# 261503933xxxx_HW-V2.net
KiCad netlist of a schematic drawn in EAGLE
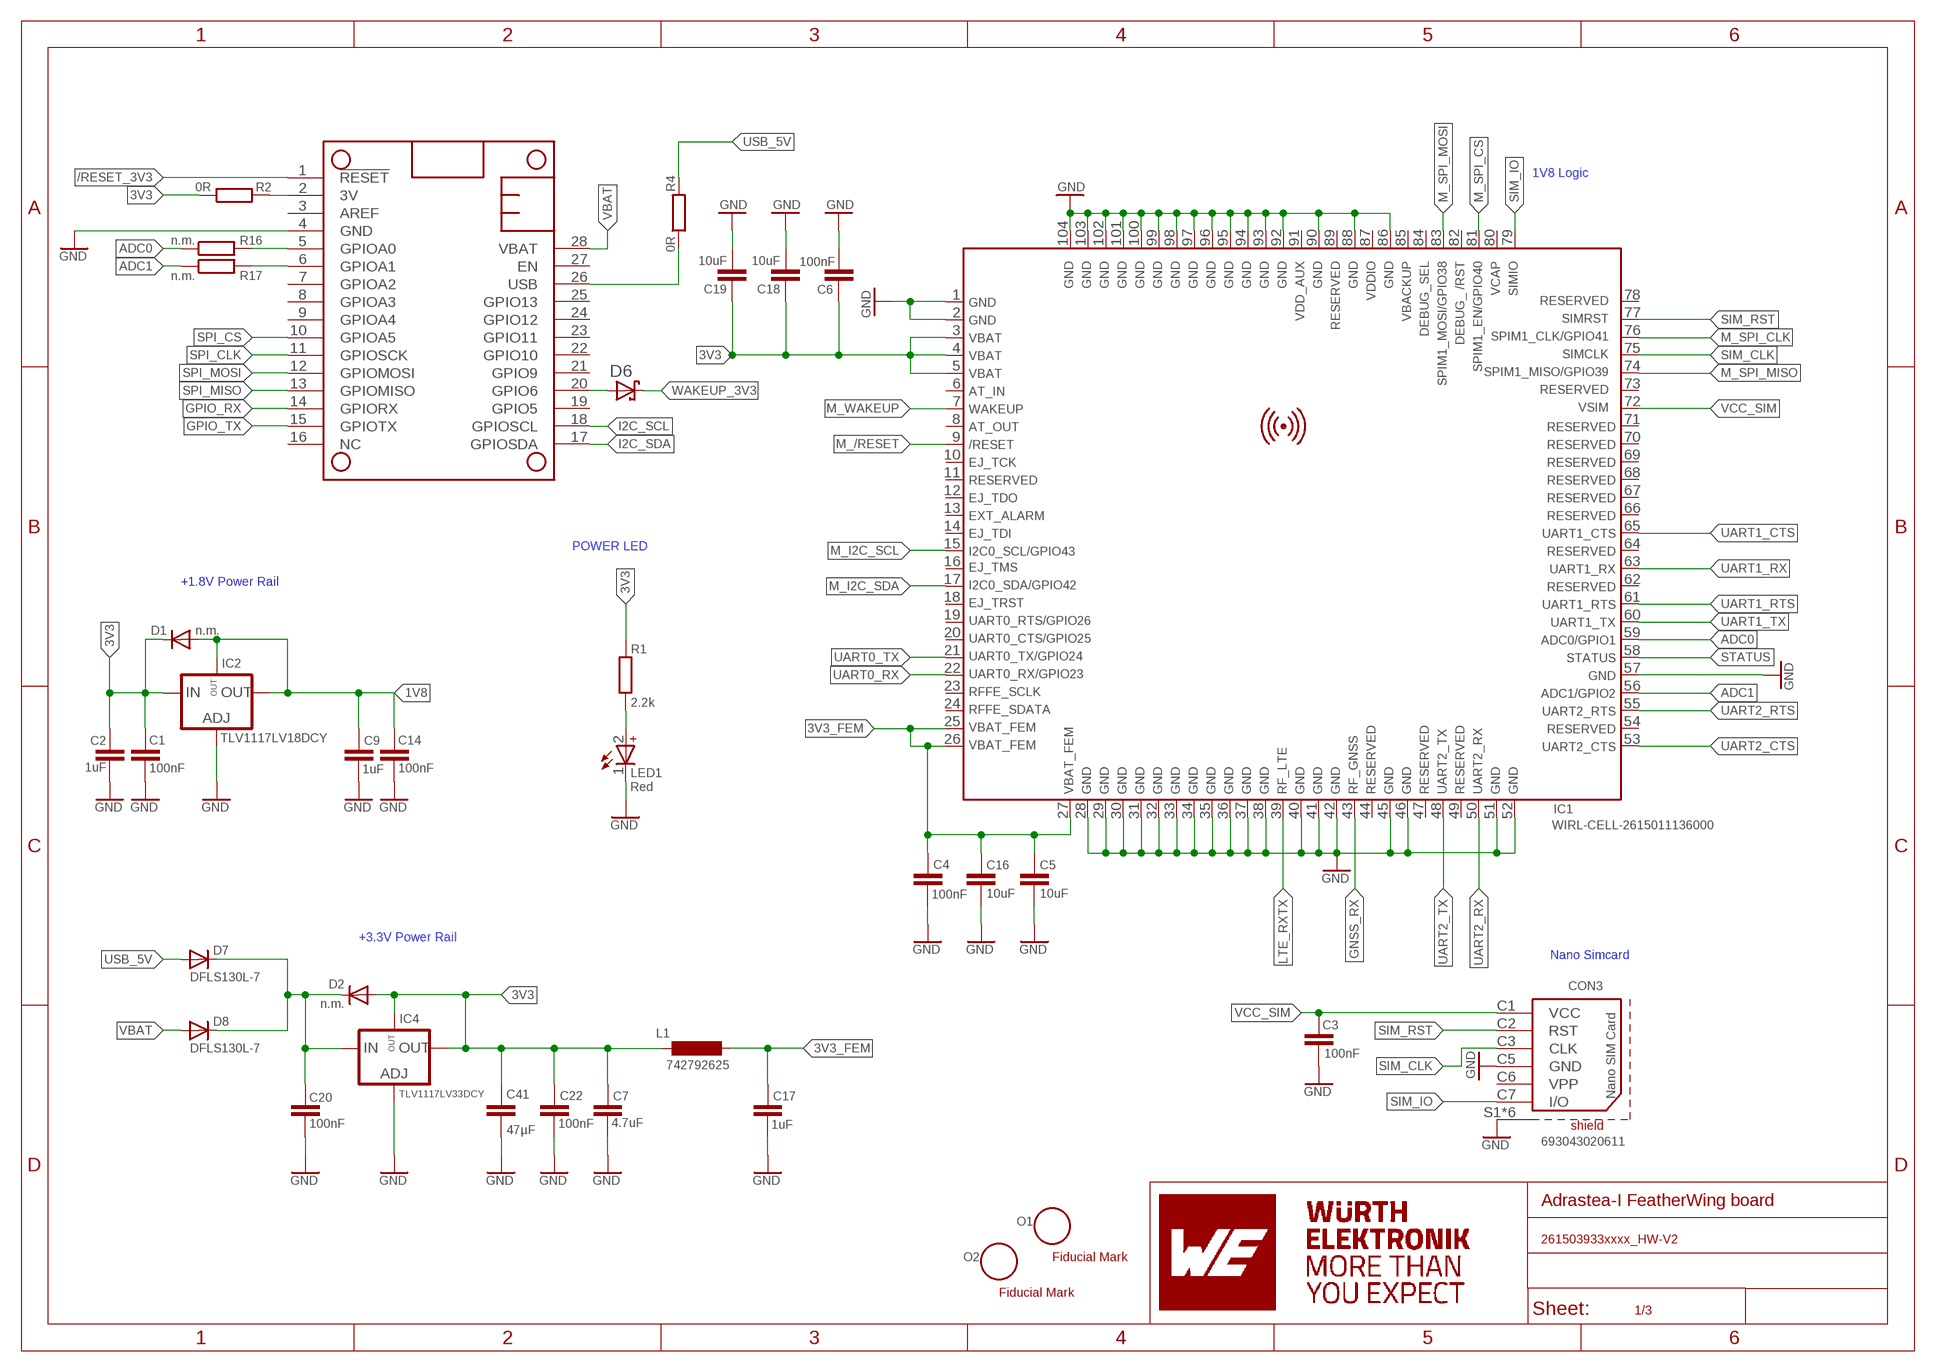
[diagram p0: schematic, sheet 1]
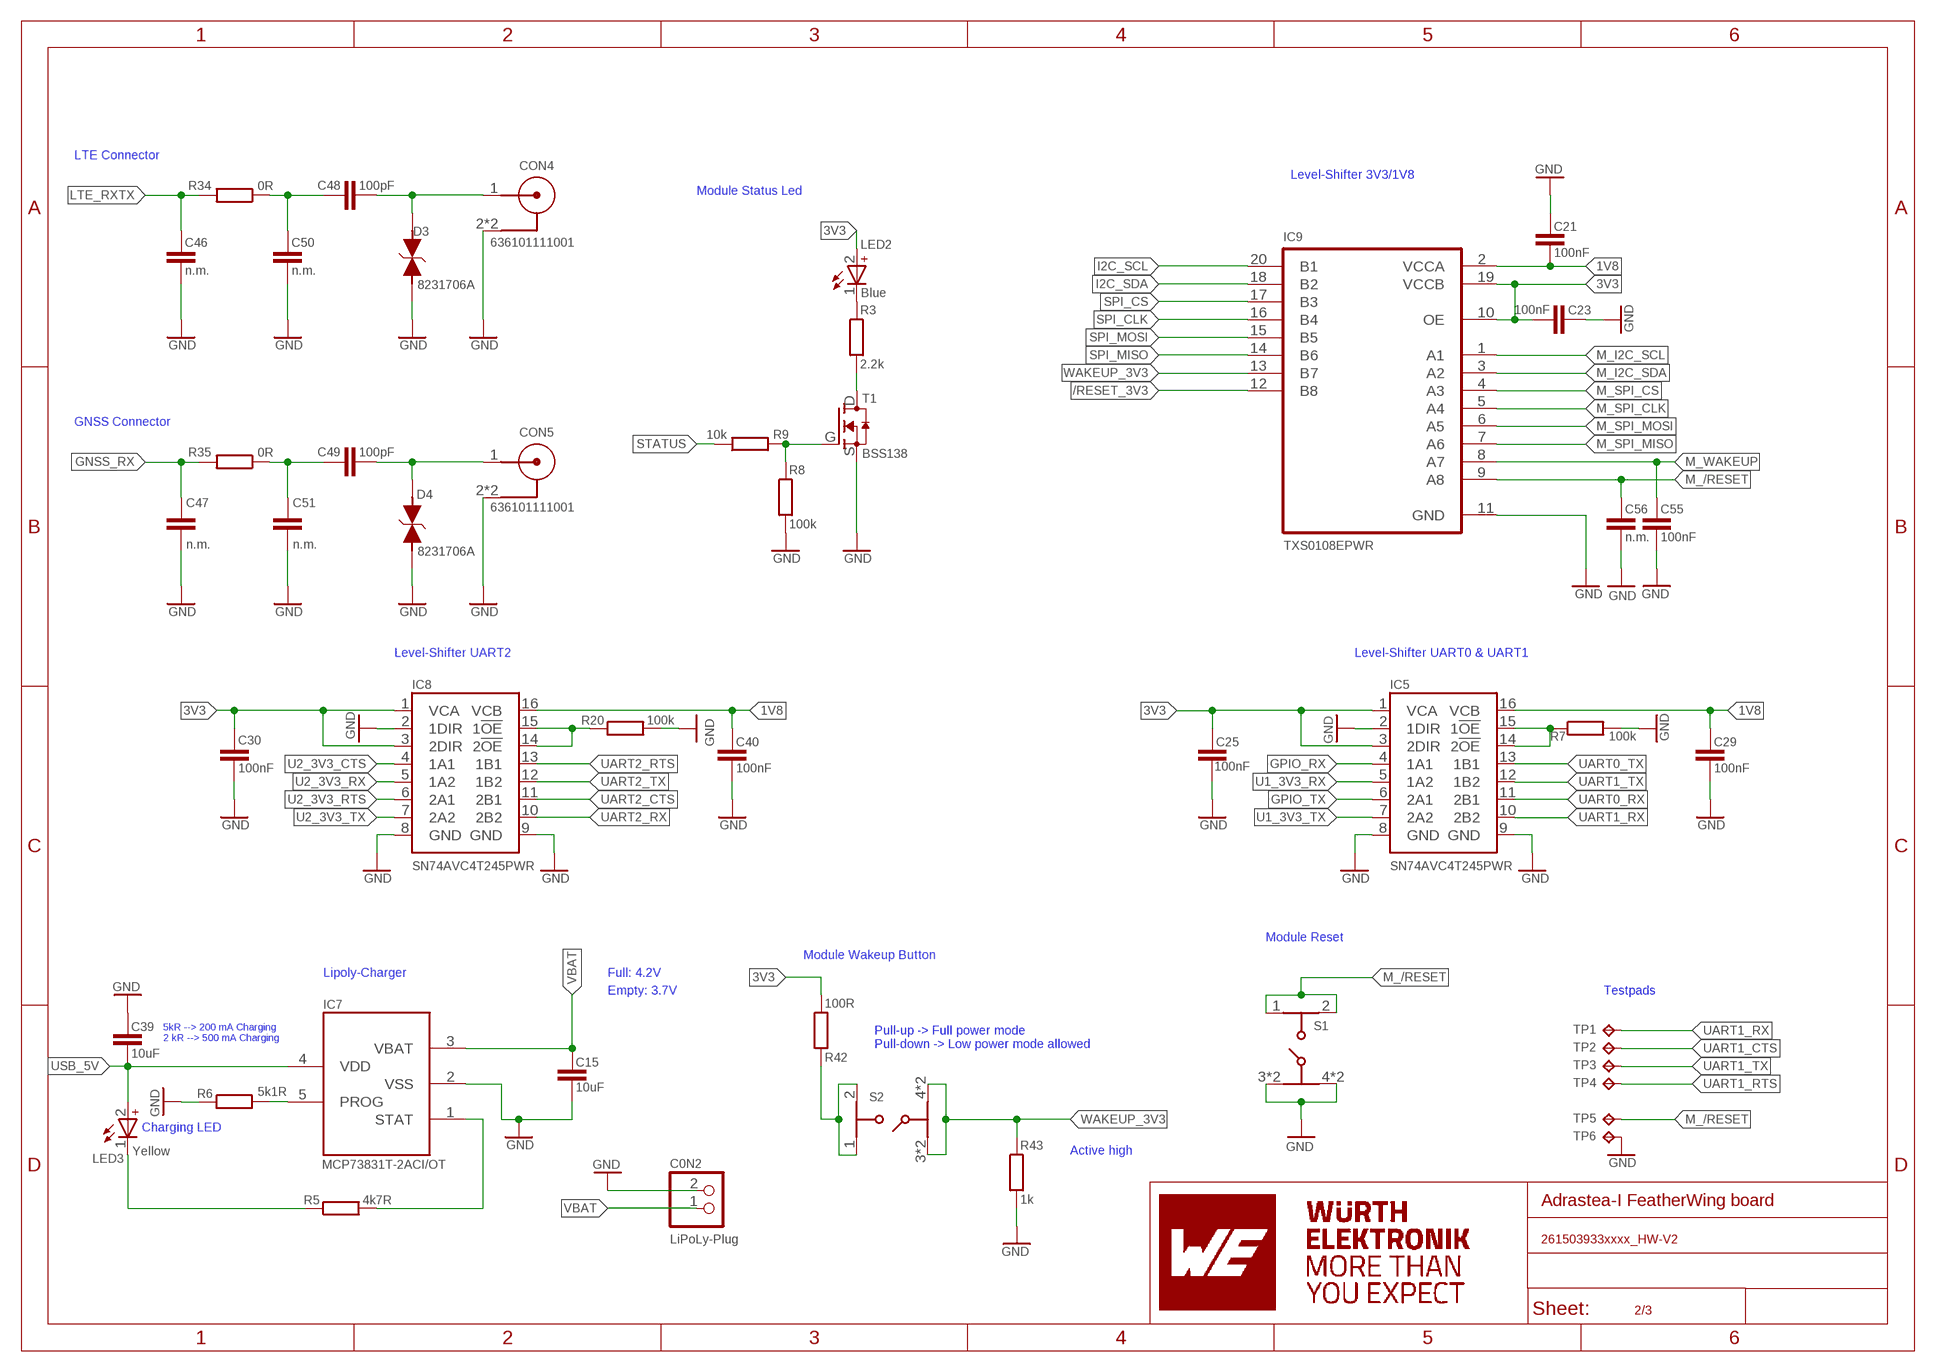
[diagram p1: schematic, sheet 2]
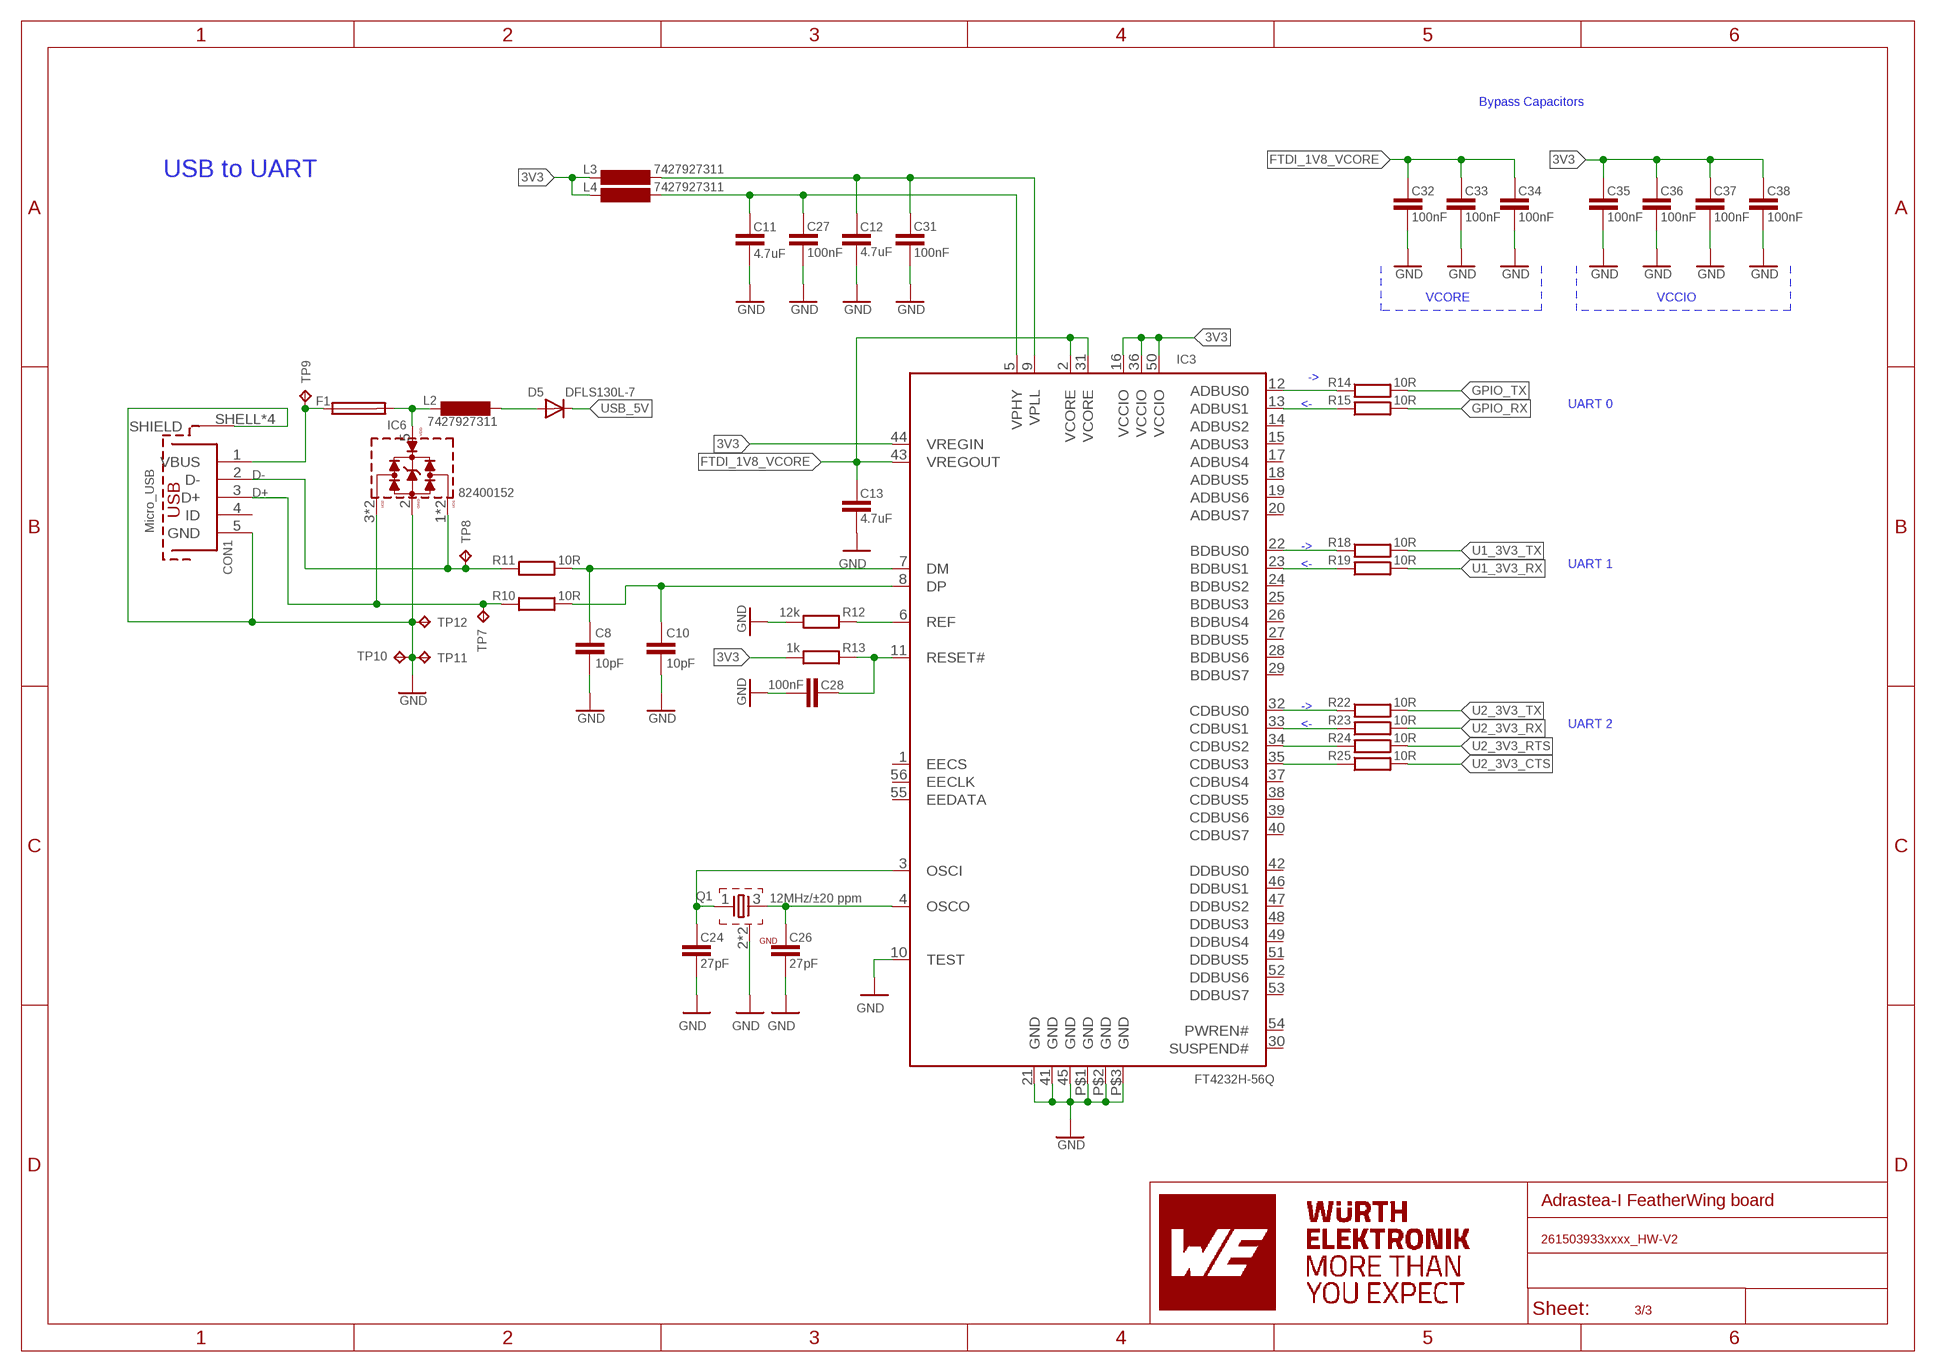
[diagram p2: schematic, sheet 3]

(export (version "E")
  (design (tool "Eeschema 10.0.6"))
  (components
    (comp (ref "C0N2")
      (value "LiPoLy-Plug")
      (footprint "eagle-import:JST-PH-2-SMT-RA-ADRASTEA-ANGEPASST")
      (fields (field (name "MANUFACTURER") "Adafruit"))
      (libsource (lib "eagle-import") (part "JST_2PIN"))
    )
    (comp (ref "C15")
      (value "10uF")
      (footprint "eagle-import:C0402_IPC")
      (fields (field (name "MANUFACTURER") "Würth Elektronik"))
      (libsource (lib "eagle-import") (part "C0402_IPC10UF"))
    )
    (comp (ref "C21")
      (value "100nF")
      (footprint "eagle-import:C0402_IPC")
      (fields
        (field (name "MANUFACTURER") "Würth Elektronik")
        (field (name "MAT") "X7R")
        (field (name "NR") "885012205037")
        (field (name "SPG") "16V")
        (field (name "TOL") "10%")
      )
      (libsource (lib "eagle-import") (part "rcl-amber_C0402_IPC"))
    )
    (comp (ref "C23")
      (value "100nF")
      (footprint "eagle-import:C0402_IPC")
      (fields
        (field (name "MANUFACTURER") "Würth Elektronik")
        (field (name "MAT") "X7R")
        (field (name "NR") "885012205037")
        (field (name "SPG") "16V")
        (field (name "TOL") "10%")
      )
      (libsource (lib "eagle-import") (part "rcl-amber_C0402_IPC"))
    )
    (comp (ref "C25")
      (value "100nF")
      (footprint "eagle-import:C0402_IPC")
      (fields
        (field (name "MANUFACTURER") "Würth Elektronik")
        (field (name "MAT") "X7R")
        (field (name "NR") "885012205037")
        (field (name "SPG") "16V")
        (field (name "TOL") "10%")
      )
      (libsource (lib "eagle-import") (part "rcl-amber_C0402_IPC"))
    )
    (comp (ref "C29")
      (value "100nF")
      (footprint "eagle-import:C0402_IPC")
      (fields
        (field (name "MANUFACTURER") "Würth Elektronik")
        (field (name "MAT") "X7R")
        (field (name "NR") "885012205037")
        (field (name "SPG") "16V")
        (field (name "TOL") "10%")
      )
      (libsource (lib "eagle-import") (part "rcl-amber_C0402_IPC"))
    )
    (comp (ref "C30")
      (value "100nF")
      (footprint "eagle-import:C0402_IPC")
      (fields
        (field (name "MANUFACTURER") "Würth Elektronik")
        (field (name "MAT") "X7R")
        (field (name "NR") "885012205037")
        (field (name "SPG") "16V")
        (field (name "TOL") "10%")
      )
      (libsource (lib "eagle-import") (part "rcl-amber_C0402_IPC"))
    )
    (comp (ref "C39")
      (value "10uF")
      (footprint "eagle-import:C0603_IPC")
      (fields (field (name "MANUFACTURER") "Wurth Elektronik") (field (name "NR") "885012106031"))
      (libsource (lib "eagle-import") (part "C0603_IPC1UF"))
    )
    (comp (ref "C40")
      (value "100nF")
      (footprint "eagle-import:C0402_IPC")
      (fields
        (field (name "MANUFACTURER") "Würth Elektronik")
        (field (name "MAT") "X7R")
        (field (name "NR") "885012205037")
        (field (name "SPG") "16V")
        (field (name "TOL") "10%")
      )
      (libsource (lib "eagle-import") (part "rcl-amber_C0402_IPC"))
    )
    (comp (ref "C46")
      (value "n.m.")
      (footprint "eagle-import:C0402_IPC")
      (fields (field (name "MANUFACTURER") "n.m.") (field (name "NR") "n.m."))
      (libsource (lib "eagle-import") (part "rcl-amber_C0402_IPC"))
    )
    (comp (ref "C47")
      (value "n.m.")
      (footprint "eagle-import:C0402_IPC")
      (fields (field (name "MANUFACTURER") "n.m.") (field (name "NR") "n.m."))
      (libsource (lib "eagle-import") (part "rcl-amber_C0402_IPC"))
    )
    (comp (ref "C48")
      (value "100pF")
      (footprint "eagle-import:C0402_IPC")
      (fields
        (field (name "MANUFACTURER") "Yageo")
        (field (name "MANUFACTURER_1") "Würth Elektronik")
        (field (name "MAT") "NP0")
        (field (name "NR") "885012005061")
      )
      (libsource (lib "eagle-import") (part "rcl-amber_C0402_IPC100PF"))
    )
    (comp (ref "C49")
      (value "100pF")
      (footprint "eagle-import:C0402_IPC")
      (fields
        (field (name "MANUFACTURER") "Würth Elektronik")
        (field (name "MAT") "NP0")
        (field (name "NR") "885012005061")
        (field (name "SPG") "50V")
        (field (name "TOL") "5%")
      )
      (libsource (lib "eagle-import") (part "rcl-amber_C0402_IPC"))
    )
    (comp (ref "C50")
      (value "n.m.")
      (footprint "eagle-import:C0402_IPC")
      (fields (field (name "MANUFACTURER") "n.m.") (field (name "NR") "n.m."))
      (libsource (lib "eagle-import") (part "rcl-amber_C0402_IPC"))
    )
    (comp (ref "C51")
      (value "n.m.")
      (footprint "eagle-import:C0402_IPC")
      (fields (field (name "MANUFACTURER") "n.m.") (field (name "NR") "n.m."))
      (libsource (lib "eagle-import") (part "rcl-amber_C0402_IPC"))
    )
    (comp (ref "C55")
      (value "100nF")
      (footprint "eagle-import:C0402_IPC")
      (fields
        (field (name "MANUFACTURER") "Würth Elektronik")
        (field (name "MAT") "X7R")
        (field (name "NR") "885012205037")
        (field (name "SPG") "16V")
        (field (name "TOL") "10%")
      )
      (libsource (lib "eagle-import") (part "rcl-amber_C0402_IPC"))
    )
    (comp (ref "C56")
      (value "n.m.")
      (footprint "eagle-import:C0402_IPC")
      (fields (field (name "MANUFACTURER") "n.m.") (field (name "NR") "n.m."))
      (libsource (lib "eagle-import") (part "rcl-amber_C0402_IPC"))
    )
    (comp (ref "CON4")
      (value "636101111001")
      (footprint "eagle-import:636101111001")
      (libsource (lib "eagle-import") (part "636101111001"))
    )
    (comp (ref "CON5")
      (value "636101111001")
      (footprint "eagle-import:636101111001")
      (libsource (lib "eagle-import") (part "636101111001"))
    )
    (comp (ref "D3")
      (value "8231706A")
      (footprint "eagle-import:WE-VE_FEMTOF_0402")
      (fields (field (name "MANUFACTURER") "Würth Elektronik"))
      (libsource (lib "eagle-import") (part "WE-VE_FEMTOF_0402_8231714A"))
    )
    (comp (ref "D4")
      (value "8231706A")
      (footprint "eagle-import:WE-VE_FEMTOF_0402")
      (fields (field (name "MANUFACTURER") "Würth Elektronik"))
      (libsource (lib "eagle-import") (part "WE-VE_FEMTOF_0402_8231714A"))
    )
    (comp (ref "IC5")
      (value "SN74AVC4T245PWR")
      (footprint "eagle-import:PW16(TSSOP16)")
      (fields (field (name "MANUFACTURER") "Texas Instruments"))
      (libsource (lib "eagle-import") (part "SN74AVC4T245PWR"))
    )
    (comp (ref "IC7")
      (value "MCP73831T-2ACI/OT")
      (footprint "eagle-import:SOT23-5")
      (fields (field (name "MANUFACTURER") "microchip"))
      (libsource (lib "eagle-import") (part "MCP73831T-2ACI/OT"))
    )
    (comp (ref "IC8")
      (value "SN74AVC4T245PWR")
      (footprint "eagle-import:PW16(TSSOP16)")
      (fields (field (name "MANUFACTURER") "Texas Instruments"))
      (libsource (lib "eagle-import") (part "SN74AVC4T245PWR"))
    )
    (comp (ref "IC9")
      (value "TXS0108EPWR")
      (footprint "eagle-import:SOP65P640X120-20N")
      (fields (field (name "MF") "Texas Instruments"))
      (libsource (lib "eagle-import") (part "TXS0108EPWR"))
    )
    (comp (ref "LED2")
      (value "Blue")
      (footprint "eagle-import:WL-SMSW_1204_A")
      (fields (field (name "MANUFACTURER") "würth elektronik"))
      (libsource (lib "eagle-import") (part "WL-SMSW_1204_155124BS73200"))
    )
    (comp (ref "LED3")
      (value "Yellow")
      (footprint "eagle-import:WL-SMSW_1204_A")
      (fields (field (name "MANUFACTURER") "würth elektronik"))
      (libsource (lib "eagle-import") (part "WL-SMSW_1204_155124RS73200"))
    )
    (comp (ref "R3")
      (value "2.2k")
      (footprint "eagle-import:R0402_IPC")
      (fields (field (name "MANUFACTURER") "Yageo") (field (name "P") "1/16W"))
      (libsource (lib "eagle-import") (part "R0402_IPC2K2"))
    )
    (comp (ref "R5")
      (value "4k7R")
      (footprint "eagle-import:R0402_IPC")
      (fields (field (name "MANUFACTURER") "Yageo"))
      (libsource (lib "eagle-import") (part "R0402_IPC4K7"))
    )
    (comp (ref "R6")
      (value "5k1R")
      (footprint "eagle-import:R0402_IPC")
      (fields (field (name "NR") " RC0402FR-075K1L"))
      (libsource (lib "eagle-import") (part "R0402_IPC56R"))
    )
    (comp (ref "R7")
      (value "100k")
      (footprint "eagle-import:R0402_IPC")
      (libsource (lib "eagle-import") (part "R0402_IPC100KR"))
    )
    (comp (ref "R8")
      (value "100k")
      (footprint "eagle-import:R0402_IPC")
      (fields (field (name "MANUFACTURER") "Yageo") (field (name "P") "1/16W"))
      (libsource (lib "eagle-import") (part "rcl-amber_R0402_IPC100KR"))
    )
    (comp (ref "R9")
      (value "10k")
      (footprint "eagle-import:R0402_IPC")
      (fields (field (name "MANUFACTURER") "Yageo") (field (name "P") "1/16W"))
      (libsource (lib "eagle-import") (part "rcl-amber_R0402_IPC10KR"))
    )
    (comp (ref "R20")
      (value "100k")
      (footprint "eagle-import:R0402_IPC")
      (libsource (lib "eagle-import") (part "R0402_IPC100KR"))
    )
    (comp (ref "R34")
      (value "0R")
      (footprint "eagle-import:R0402_IPC")
      (fields (field (name "MANUFACTURER") "Yageo") (field (name "P") "1/16W"))
      (libsource (lib "eagle-import") (part "rcl-amber_R0402_IPC0R"))
    )
    (comp (ref "R35")
      (value "0R")
      (footprint "eagle-import:R0402_IPC")
      (fields (field (name "MANUFACTURER") "Yageo") (field (name "P") "1/16W"))
      (libsource (lib "eagle-import") (part "rcl-amber_R0402_IPC0R"))
    )
    (comp (ref "R42")
      (value "100R")
      (footprint "eagle-import:R0402_IPC")
      (fields (field (name "MANUFACTURER") "Yageo"))
      (libsource (lib "eagle-import") (part "R0402_IPC100R"))
    )
    (comp (ref "R43")
      (value "1k")
      (footprint "eagle-import:R0402_IPC")
      (fields (field (name "MANUFACTURER") "Yageo") (field (name "P") "1/16W"))
      (libsource (lib "eagle-import") (part "R0402_IPC1K"))
    )
    (comp (ref "S1")
      (value "434331013822")
      (footprint "eagle-import:434331013822")
      (libsource (lib "eagle-import") (part "434331013822"))
    )
    (comp (ref "S2")
      (value "434331013822")
      (footprint "eagle-import:434331013822")
      (libsource (lib "eagle-import") (part "434331013822"))
    )
    (comp (ref "T1")
      (value "BSS138")
      (footprint "eagle-import:BSS138")
      (fields (field (name "MANUFACTURER") "ON seminconductor"))
      (libsource (lib "eagle-import") (part "BSS138"))
    )
    (comp (ref "TP1")
      (value "TP15R")
      (footprint "eagle-import:TP15R")
      (libsource (lib "eagle-import") (part "TP15R"))
    )
    (comp (ref "TP2")
      (value "TP15R")
      (footprint "eagle-import:TP15R")
      (libsource (lib "eagle-import") (part "TP15R"))
    )
    (comp (ref "TP3")
      (value "TP15R")
      (footprint "eagle-import:TP15R")
      (libsource (lib "eagle-import") (part "TP15R"))
    )
    (comp (ref "TP4")
      (value "TP15R")
      (footprint "eagle-import:TP15R")
      (libsource (lib "eagle-import") (part "TP15R"))
    )
    (comp (ref "TP5")
      (value "TP15R")
      (footprint "eagle-import:TP15R")
      (libsource (lib "eagle-import") (part "TP15R"))
    )
    (comp (ref "TP6")
      (value "TP15R")
      (footprint "eagle-import:TP15R")
      (libsource (lib "eagle-import") (part "TP15R"))
    )
    (comp (ref "C8")
      (value "10pF")
      (footprint "eagle-import:C0402_IPC")
      (fields (field (name "MANUFACTURER") "Würth Elektronik") (field (name "MAT") "NP0"))
      (libsource (lib "eagle-import") (part "C0402_IPC10PF"))
    )
    (comp (ref "C10")
      (value "10pF")
      (footprint "eagle-import:C0402_IPC")
      (fields (field (name "MANUFACTURER") "Würth Elektronik") (field (name "MAT") "NP0"))
      (libsource (lib "eagle-import") (part "C0402_IPC10PF"))
    )
    (comp (ref "C11")
      (value "4.7uF")
      (footprint "eagle-import:C0402_IPC")
      (fields (field (name "MANUFACTURER") "Würth Elektronik"))
      (libsource (lib "eagle-import") (part "C0402_IPC4.7UF"))
    )
    (comp (ref "C12")
      (value "4.7uF")
      (footprint "eagle-import:C0402_IPC")
      (fields (field (name "MANUFACTURER") "Würth Elektronik"))
      (libsource (lib "eagle-import") (part "C0402_IPC4.7UF"))
    )
    (comp (ref "C13")
      (value "4.7uF")
      (footprint "eagle-import:C0402_IPC")
      (fields (field (name "MANUFACTURER") "Würth Elektronik"))
      (libsource (lib "eagle-import") (part "C0402_IPC4.7UF"))
    )
    (comp (ref "C24")
      (value "27pF")
      (footprint "eagle-import:C0402_IPC")
      (fields
        (field (name "MANUFACTURER") "Yageo")
        (field (name "MANUFACTURER_1") "Samsung")
        (field (name "NR") "CL05C270JB5NNNC")
      )
      (libsource (lib "eagle-import") (part "C0402_IPC27P"))
    )
    (comp (ref "C26")
      (value "27pF")
      (footprint "eagle-import:C0402_IPC")
      (fields
        (field (name "MANUFACTURER") "Yageo")
        (field (name "MANUFACTURER_1") "Samsung")
        (field (name "NR") "CL05C270JB5NNNC")
      )
      (libsource (lib "eagle-import") (part "C0402_IPC27P"))
    )
    (comp (ref "C27")
      (value "100nF")
      (footprint "eagle-import:C0402_IPC")
      (fields
        (field (name "MANUFACTURER") "Würth Elektronik")
        (field (name "MAT") "X7R")
        (field (name "NR") "885012205037")
        (field (name "SPG") "16V")
        (field (name "TOL") "10%")
      )
      (libsource (lib "eagle-import") (part "rcl-amber_C0402_IPC"))
    )
    (comp (ref "C28")
      (value "100nF")
      (footprint "eagle-import:C0402_IPC")
      (fields
        (field (name "MANUFACTURER") "Würth Elektronik")
        (field (name "MAT") "X7R")
        (field (name "NR") "885012205037")
        (field (name "SPG") "16V")
        (field (name "TOL") "10%")
      )
      (libsource (lib "eagle-import") (part "rcl-amber_C0402_IPC"))
    )
    (comp (ref "C31")
      (value "100nF")
      (footprint "eagle-import:C0402_IPC")
      (fields
        (field (name "MANUFACTURER") "Würth Elektronik")
        (field (name "MAT") "X7R")
        (field (name "NR") "885012205037")
        (field (name "SPG") "16V")
        (field (name "TOL") "10%")
      )
      (libsource (lib "eagle-import") (part "rcl-amber_C0402_IPC"))
    )
    (comp (ref "C32")
      (value "100nF")
      (footprint "eagle-import:C0402_IPC")
      (fields
        (field (name "MANUFACTURER") "Würth Elektronik")
        (field (name "MAT") "X7R")
        (field (name "NR") "885012205037")
        (field (name "SPG") "16V")
        (field (name "TOL") "10%")
      )
      (libsource (lib "eagle-import") (part "rcl-amber_C0402_IPC"))
    )
    (comp (ref "C33")
      (value "100nF")
      (footprint "eagle-import:C0402_IPC")
      (fields
        (field (name "MANUFACTURER") "Würth Elektronik")
        (field (name "MAT") "X7R")
        (field (name "NR") "885012205037")
        (field (name "SPG") "16V")
        (field (name "TOL") "10%")
      )
      (libsource (lib "eagle-import") (part "rcl-amber_C0402_IPC"))
    )
    (comp (ref "C34")
      (value "100nF")
      (footprint "eagle-import:C0402_IPC")
      (fields
        (field (name "MANUFACTURER") "Würth Elektronik")
        (field (name "MAT") "X7R")
        (field (name "NR") "885012205037")
        (field (name "SPG") "16V")
        (field (name "TOL") "10%")
      )
      (libsource (lib "eagle-import") (part "rcl-amber_C0402_IPC"))
    )
    (comp (ref "C35")
      (value "100nF")
      (footprint "eagle-import:C0402_IPC")
      (fields
        (field (name "MANUFACTURER") "Würth Elektronik")
        (field (name "MAT") "X7R")
        (field (name "NR") "885012205037")
        (field (name "SPG") "16V")
        (field (name "TOL") "10%")
      )
      (libsource (lib "eagle-import") (part "rcl-amber_C0402_IPC"))
    )
    (comp (ref "C36")
      (value "100nF")
      (footprint "eagle-import:C0402_IPC")
      (fields
        (field (name "MANUFACTURER") "Würth Elektronik")
        (field (name "MAT") "X7R")
        (field (name "NR") "885012205037")
        (field (name "SPG") "16V")
        (field (name "TOL") "10%")
      )
      (libsource (lib "eagle-import") (part "rcl-amber_C0402_IPC"))
    )
    (comp (ref "C37")
      (value "100nF")
      (footprint "eagle-import:C0402_IPC")
      (fields
        (field (name "MANUFACTURER") "Würth Elektronik")
        (field (name "MAT") "X7R")
        (field (name "NR") "885012205037")
        (field (name "SPG") "16V")
        (field (name "TOL") "10%")
      )
      (libsource (lib "eagle-import") (part "rcl-amber_C0402_IPC"))
    )
    (comp (ref "C38")
      (value "100nF")
      (footprint "eagle-import:C0402_IPC")
      (fields
        (field (name "MANUFACTURER") "Würth Elektronik")
        (field (name "MAT") "X7R")
        (field (name "NR") "885012205037")
        (field (name "SPG") "16V")
        (field (name "TOL") "10%")
      )
      (libsource (lib "eagle-import") (part "rcl-amber_C0402_IPC"))
    )
    (comp (ref "CON1")
      (value "Micro_USB")
      (footprint "eagle-import:629105150521")
      (fields
        (field (name "COMMENT") "Use selective soldering")
        (field (name "MANUFACTURER") "Würth Elektronik")
      )
      (libsource (lib "eagle-import") (part "629105150521"))
    )
    (comp (ref "D5")
      (value "DFLS130L-7")
      (footprint "eagle-import:SOD123_POWERDI")
      (fields (field (name "MANUFACTURER") "diodes inc"))
      (libsource (lib "eagle-import") (part "DFLS130L-7"))
    )
    (comp (ref "F1")
      (value "ERB-RD1R50X")
      (footprint "eagle-import:0402")
      (fields (field (name "MANUFACTURER") "Panasonic"))
      (libsource (lib "eagle-import") (part "ERB-RD1R50X"))
    )
    (comp (ref "IC3")
      (value "FT4232H-56Q")
      (footprint "eagle-import:VQFN-56")
      (fields (field (name "MANUFACTURER") "FTDI"))
      (libsource (lib "eagle-import") (part "FT4232H-56Q"))
    )
    (comp (ref "IC6")
      (value "82400152")
      (footprint "eagle-import:WE-TVS_SOT563")
      (fields (field (name "MANUFACTURER") "Würth Elektronik"))
      (libsource (lib "eagle-import") (part "WE-TVS_82400152"))
    )
    (comp (ref "L2")
      (value "7427927311")
      (footprint "eagle-import:L0402_WE-MK")
      (fields
        (field (name "MANUFACTURER") "Tayo Yuden")
        (field (name "MANUFACTURER_1") "Würth Elektronik")
        (field (name "NR") "7427927311")
      )
      (libsource (lib "eagle-import") (part "LL0402_WE-MK"))
    )
    (comp (ref "L3")
      (value "7427927311")
      (footprint "eagle-import:L0402_WE-MK")
      (fields
        (field (name "MANUFACTURER") "Tayo Yuden")
        (field (name "MANUFACTURER_1") "Würth Elektronik")
        (field (name "NR") "7427927311")
      )
      (libsource (lib "eagle-import") (part "LL0402_WE-MK"))
    )
    (comp (ref "L4")
      (value "7427927311")
      (footprint "eagle-import:L0402_WE-MK")
      (fields
        (field (name "MANUFACTURER") "Tayo Yuden")
        (field (name "MANUFACTURER_1") "Würth Elektronik")
        (field (name "NR") "7427927311")
      )
      (libsource (lib "eagle-import") (part "LL0402_WE-MK"))
    )
    (comp (ref "Q1")
      (value "12MHz/±20 ppm")
      (footprint "eagle-import:WE-XTAL_CFPX-180")
      (fields (field (name "MANUFACTURER") "Würth Elektronik"))
      (libsource (lib "eagle-import") (part "WE-XTAL_CFPX-180_830070868"))
    )
    (comp (ref "R10")
      (value "10R")
      (footprint "eagle-import:R0402_IPC")
      (fields (field (name "MANUFACTURER") "Yageo"))
      (libsource (lib "eagle-import") (part "rcl-amber_R0402_IPC10R"))
    )
    (comp (ref "R11")
      (value "10R")
      (footprint "eagle-import:R0402_IPC")
      (fields (field (name "MANUFACTURER") "Yageo"))
      (libsource (lib "eagle-import") (part "rcl-amber_R0402_IPC10R"))
    )
    (comp (ref "R12")
      (value "12k")
      (footprint "eagle-import:R0402_IPC")
      (fields (field (name "MANUFACTURER") "Yageo") (field (name "P") "1/16W"))
      (libsource (lib "eagle-import") (part "R0402_IPC12K"))
    )
    (comp (ref "R13")
      (value "1k")
      (footprint "eagle-import:R0402_IPC")
      (fields (field (name "MANUFACTURER") "Yageo"))
      (libsource (lib "eagle-import") (part "R0402_IPC1K"))
    )
    (comp (ref "R14")
      (value "10R")
      (footprint "eagle-import:R0402_IPC")
      (fields (field (name "MANUFACTURER") "Yageo"))
      (libsource (lib "eagle-import") (part "rcl-amber_R0402_IPC10R"))
    )
    (comp (ref "R15")
      (value "10R")
      (footprint "eagle-import:R0402_IPC")
      (fields (field (name "MANUFACTURER") "Yageo"))
      (libsource (lib "eagle-import") (part "rcl-amber_R0402_IPC10R"))
    )
    (comp (ref "R18")
      (value "10R")
      (footprint "eagle-import:R0402_IPC")
      (fields (field (name "MANUFACTURER") "Yageo"))
      (libsource (lib "eagle-import") (part "rcl-amber_R0402_IPC10R"))
    )
    (comp (ref "R19")
      (value "10R")
      (footprint "eagle-import:R0402_IPC")
      (fields (field (name "MANUFACTURER") "Yageo"))
      (libsource (lib "eagle-import") (part "rcl-amber_R0402_IPC10R"))
    )
    (comp (ref "R22")
      (value "10R")
      (footprint "eagle-import:R0402_IPC")
      (fields (field (name "MANUFACTURER") "Yageo"))
      (libsource (lib "eagle-import") (part "rcl-amber_R0402_IPC10R"))
    )
    (comp (ref "R23")
      (value "10R")
      (footprint "eagle-import:R0402_IPC")
      (fields (field (name "MANUFACTURER") "Yageo"))
      (libsource (lib "eagle-import") (part "rcl-amber_R0402_IPC10R"))
    )
    (comp (ref "R24")
      (value "10R")
      (footprint "eagle-import:R0402_IPC")
      (fields (field (name "MANUFACTURER") "Yageo"))
      (libsource (lib "eagle-import") (part "rcl-amber_R0402_IPC10R"))
    )
    (comp (ref "R25")
      (value "10R")
      (footprint "eagle-import:R0402_IPC")
      (fields (field (name "MANUFACTURER") "Yageo"))
      (libsource (lib "eagle-import") (part "rcl-amber_R0402_IPC10R"))
    )
    (comp (ref "TP7")
      (value "TP15R")
      (footprint "eagle-import:TP15R")
      (libsource (lib "eagle-import") (part "TP15R"))
    )
    (comp (ref "TP8")
      (value "TP15R")
      (footprint "eagle-import:TP15R")
      (libsource (lib "eagle-import") (part "TP15R"))
    )
    (comp (ref "TP9")
      (value "TP15R")
      (footprint "eagle-import:TP15R")
      (libsource (lib "eagle-import") (part "TP15R"))
    )
    (comp (ref "TP10")
      (value "TP15R")
      (footprint "eagle-import:TP15R")
      (libsource (lib "eagle-import") (part "TP15R"))
    )
    (comp (ref "TP11")
      (value "TP15R")
      (footprint "eagle-import:TP15R")
      (libsource (lib "eagle-import") (part "TP15R"))
    )
    (comp (ref "TP12")
      (value "TP15R")
      (footprint "eagle-import:TP15R")
      (libsource (lib "eagle-import") (part "TP15R"))
    )
    (comp (ref "C1")
      (value "100nF")
      (footprint "eagle-import:C0402_IPC")
      (fields
        (field (name "MANUFACTURER") "Würth Elektronik")
        (field (name "MAT") "X7R")
        (field (name "NR") "885012205037")
        (field (name "SPG") "16V")
        (field (name "TOL") "10%")
      )
      (libsource (lib "eagle-import") (part "rcl-amber_C0402_IPC"))
    )
    (comp (ref "C2")
      (value "1uF")
      (footprint "eagle-import:C0402_IPC")
      (fields (field (name "MANUFACTURER") "Würth Elektronik"))
      (libsource (lib "eagle-import") (part "C0402_IPC1UF"))
    )
    (comp (ref "C3")
      (value "100nF")
      (footprint "eagle-import:C0402_IPC")
      (fields (field (name "MANUFACTURER") "Würth Elektronik"))
      (libsource (lib "eagle-import") (part "C0402_IPC100NF"))
    )
    (comp (ref "C4")
      (value "100nF")
      (footprint "eagle-import:C0402_IPC")
      (fields
        (field (name "MANUFACTURER") "Würth Elektronik")
        (field (name "MAT") "X7R")
        (field (name "NR") "885012205037")
        (field (name "SPG") "16V")
        (field (name "TOL") "10%")
      )
      (libsource (lib "eagle-import") (part "rcl-amber_C0402_IPC"))
    )
    (comp (ref "C5")
      (value "10uF")
      (footprint "eagle-import:C0402_IPC")
      (fields
        (field (name "MANUFACTURER") "Würth Elektronik")
        (field (name "NR") "885012105020")
        (field (name "SPG") "6,3V")
      )
      (libsource (lib "eagle-import") (part "C0402_IPC"))
    )
    (comp (ref "C6")
      (value "100nF")
      (footprint "eagle-import:C0402_IPC")
      (fields
        (field (name "MANUFACTURER") "Würth Elektronik")
        (field (name "MAT") "X7R")
        (field (name "NR") "885012205037")
        (field (name "SPG") "16V")
        (field (name "TOL") "10%")
      )
      (libsource (lib "eagle-import") (part "rcl-amber_C0402_IPC"))
    )
    (comp (ref "C7")
      (value "4.7uF")
      (footprint "eagle-import:C0402_IPC")
      (fields (field (name "MANUFACTURER") "Würth Elektronik"))
      (libsource (lib "eagle-import") (part "C0402_IPC4.7UF"))
    )
    (comp (ref "C9")
      (value "1uF")
      (footprint "eagle-import:C0402_IPC")
      (fields (field (name "MANUFACTURER") "Würth Elektronik"))
      (libsource (lib "eagle-import") (part "C0402_IPC1UF"))
    )
    (comp (ref "C14")
      (value "100nF")
      (footprint "eagle-import:C0402_IPC")
      (fields
        (field (name "MANUFACTURER") "Würth Elektronik")
        (field (name "MAT") "X7R")
        (field (name "NR") "885012205037")
        (field (name "SPG") "16V")
        (field (name "TOL") "10%")
      )
      (libsource (lib "eagle-import") (part "rcl-amber_C0402_IPC"))
    )
    (comp (ref "C16")
      (value "10uF")
      (footprint "eagle-import:C0402_IPC")
      (fields
        (field (name "MANUFACTURER") "Würth Elektronik")
        (field (name "MAT") "X5R")
        (field (name "NR") "885012105020")
        (field (name "SPG") "6,3V")
        (field (name "TOL") "20%")
      )
      (libsource (lib "eagle-import") (part "C0402_IPC"))
    )
    (comp (ref "C17")
      (value "1uF")
      (footprint "eagle-import:C0402_IPC")
      (fields (field (name "MANUFACTURER") "Würth Elektronik"))
      (libsource (lib "eagle-import") (part "C0402_IPC1UF"))
    )
    (comp (ref "C18")
      (value "10uF")
      (footprint "eagle-import:C0402_IPC")
      (fields
        (field (name "MANUFACTURER") "Würth Elektronik")
        (field (name "NR") "885012105020")
        (field (name "SPG") "6,3V")
      )
      (libsource (lib "eagle-import") (part "C0402_IPC"))
    )
    (comp (ref "C19")
      (value "10uF")
      (footprint "eagle-import:C0402_IPC")
      (fields
        (field (name "MANUFACTURER") "Würth Elektronik")
        (field (name "NR") "885012105020")
        (field (name "SPG") "6,3V")
      )
      (libsource (lib "eagle-import") (part "C0402_IPC"))
    )
    (comp (ref "C20")
      (value "100nF")
      (footprint "eagle-import:C0402_IPC")
      (fields
        (field (name "MANUFACTURER") "Würth Elektronik")
        (field (name "MAT") "X7R")
        (field (name "NR") "885012205037")
        (field (name "SPG") "16V")
        (field (name "TOL") "10%")
      )
      (libsource (lib "eagle-import") (part "rcl-amber_C0402_IPC"))
    )
    (comp (ref "C22")
      (value "100nF")
      (footprint "eagle-import:C0402_IPC")
      (fields
        (field (name "MANUFACTURER") "Würth Elektronik")
        (field (name "MAT") "X7R")
        (field (name "NR") "885012205037")
        (field (name "SPG") "16V")
        (field (name "TOL") "10%")
      )
      (libsource (lib "eagle-import") (part "rcl-amber_C0402_IPC"))
    )
    (comp (ref "C41")
      (value "47µF")
      (footprint "eagle-import:C0805")
      (fields (field (name "MANUFACTURER") "Wurth Elektronik"))
      (libsource (lib "eagle-import") (part "C080547UF"))
    )
    (comp (ref "CON3")
      (value "693043020611")
      (footprint "eagle-import:693043020611")
      (libsource (lib "eagle-import") (part "693043020611"))
    )
    (comp (ref "D1")
      (value "n.m.")
      (footprint "eagle-import:SOT23@1")
      (libsource (lib "eagle-import") (part "BAS16"))
    )
    (comp (ref "D2")
      (value "n.m.")
      (footprint "eagle-import:SOT23@1")
      (libsource (lib "eagle-import") (part "BAS16"))
    )
    (comp (ref "D6")
      (value "BAT540402_X1-DFN1006-2")
      (footprint "eagle-import:X1-DFN1006-2")
      (fields (field (name "MANUFACTURER") "Diodes Inc."))
      (libsource (lib "eagle-import") (part "BAT540402_X1-DFN1006-2"))
    )
    (comp (ref "D7")
      (value "DFLS130L-7")
      (footprint "eagle-import:SOD123_POWERDI")
      (fields (field (name "MANUFACTURER") "diodes inc"))
      (libsource (lib "eagle-import") (part "DFLS130L-7"))
    )
    (comp (ref "D8")
      (value "DFLS130L-7")
      (footprint "eagle-import:SOD123_POWERDI")
      (fields (field (name "MANUFACTURER") "diodes inc"))
      (libsource (lib "eagle-import") (part "DFLS130L-7"))
    )
    (comp (ref "IC1")
      (value "WIRL-CELL-2615011136000")
      (footprint "eagle-import:WIRL-CELL-2615011136000")
      (fields (field (name "MANUFACTURER") "Wuerth Elektronik"))
      (libsource (lib "eagle-import") (part "WIRL-CELL-2615011136000"))
    )
    (comp (ref "IC2")
      (value "TLV1117LV18DCY")
      (footprint "eagle-import:SOT223-4")
      (fields (field (name "MANUFACTURER") "Texas Instruments"))
      (libsource (lib "eagle-import") (part "TLV1117-XXIDCYR"))
    )
    (comp (ref "IC4")
      (value "TLV1117LV33DCY")
      (footprint "eagle-import:SOT223-4")
      (fields (field (name "MANUFACTURER") "Texas Instruments"))
      (libsource (lib "eagle-import") (part "TLV1117-XXIDCYR"))
    )
    (comp (ref "L1")
      (value "742792625")
      (footprint "eagle-import:L0603_WE-MK")
      (fields
        (field (name "ISAT") "1.5A")
        (field (name "MANUFACTURER") "Würth Elektronik")
        (field (name "NR") "742792625")
        (field (name "RDC") "0.05R")
        (field (name "TOL") "25%")
      )
      (libsource (lib "eagle-import") (part "LL0603_WE-MK"))
    )
    (comp (ref "LED1")
      (value "Red")
      (footprint "eagle-import:WL-SMSW_1204_A")
      (fields (field (name "MANUFACTURER") "würth elektronik"))
      (libsource (lib "eagle-import") (part "WL-SMSW_1204_155124RS73200"))
    )
    (comp (ref "MS1")
      (value "FEATHERWING_80MM")
      (footprint "eagle-import:FEATHERWING_80MM")
      (libsource (lib "eagle-import") (part "FEATHERWING_80MM"))
    )
    (comp (ref "O1")
      (value "OPT_MARKE05")
      (footprint "eagle-import:OPT_M_05")
      (libsource (lib "eagle-import") (part "OPT_MARKE05"))
    )
    (comp (ref "O2")
      (value "OPT_MARKE05")
      (footprint "eagle-import:OPT_M_05")
      (libsource (lib "eagle-import") (part "OPT_MARKE05"))
    )
    (comp (ref "R1")
      (value "2.2k")
      (footprint "eagle-import:R0402_IPC")
      (fields (field (name "MANUFACTURER") "Yageo"))
      (libsource (lib "eagle-import") (part "R0402_IPC2K2"))
    )
    (comp (ref "R2")
      (value "0R")
      (footprint "eagle-import:R0603_IPC")
      (fields (field (name "MANUFACTURER") "Yageo"))
      (libsource (lib "eagle-import") (part "R0603_IPC0R"))
    )
    (comp (ref "R4")
      (value "0R")
      (footprint "eagle-import:R0603_IPC")
      (fields (field (name "MANUFACTURER") "Yageo"))
      (libsource (lib "eagle-import") (part "R0603_IPC0R"))
    )
    (comp (ref "R16")
      (value "n.m.")
      (footprint "eagle-import:R0402_IPC")
      (libsource (lib "eagle-import") (part "R0402_IPC"))
    )
    (comp (ref "R17")
      (value "n.m.")
      (footprint "eagle-import:R0402_IPC")
      (libsource (lib "eagle-import") (part "R0402_IPC"))
    )
  )
  (nets
    (net (code "1") (name "1V8") (class "Default")
      (node (ref "C14") (pin "2") (pinfunction "2_2") (pintype "passive"))
      (node (ref "C21") (pin "1") (pinfunction "1_1") (pintype "passive"))
      (node (ref "C29") (pin "2") (pinfunction "2_2") (pintype "passive"))
      (node (ref "C40") (pin "2") (pinfunction "2_2") (pintype "passive"))
      (node (ref "C9") (pin "1") (pinfunction "1_1") (pintype "passive"))
      (node (ref "D1") (pin "1") (pinfunction "A_1") (pintype "passive"))
      (node (ref "IC2") (pin "2") (pinfunction "OUT_2") (pintype "passive"))
      (node (ref "IC2") (pin "4") (pinfunction "OUT_4") (pintype "bidirectional"))
      (node (ref "IC5") (pin "16") (pinfunction "VCB_16") (pintype "bidirectional"))
      (node (ref "IC8") (pin "16") (pinfunction "VCB_16") (pintype "bidirectional"))
      (node (ref "IC9") (pin "2") (pinfunction "VCCA_2") (pintype "power_in"))
    )
    (net (code "2") (name "3V3") (class "Default")
      (node (ref "C1") (pin "2") (pinfunction "2_2") (pintype "passive"))
      (node (ref "C18") (pin "1") (pinfunction "1_1") (pintype "passive"))
      (node (ref "C19") (pin "1") (pinfunction "1_1") (pintype "passive"))
      (node (ref "C2") (pin "1") (pinfunction "1_1") (pintype "passive"))
      (node (ref "C22") (pin "2") (pinfunction "2_2") (pintype "passive"))
      (node (ref "C23") (pin "1") (pinfunction "1_1") (pintype "passive"))
      (node (ref "C25") (pin "2") (pinfunction "2_2") (pintype "passive"))
      (node (ref "C30") (pin "2") (pinfunction "2_2") (pintype "passive"))
      (node (ref "C35") (pin "2") (pinfunction "2_2") (pintype "passive"))
      (node (ref "C36") (pin "2") (pinfunction "2_2") (pintype "passive"))
      (node (ref "C37") (pin "2") (pinfunction "2_2") (pintype "passive"))
      (node (ref "C38") (pin "2") (pinfunction "2_2") (pintype "passive"))
      (node (ref "C41") (pin "P$1") (pinfunction "1_P$1") (pintype "passive"))
      (node (ref "C6") (pin "2") (pinfunction "2_2") (pintype "passive"))
      (node (ref "C7") (pin "1") (pinfunction "1_1") (pintype "passive"))
      (node (ref "D1") (pin "3") (pinfunction "C_3") (pintype "passive"))
      (node (ref "D2") (pin "1") (pinfunction "A_1") (pintype "passive"))
      (node (ref "IC1") (pin "3") (pinfunction "VBAT_3") (pintype "bidirectional"))
      (node (ref "IC1") (pin "4") (pinfunction "VBAT_4") (pintype "bidirectional"))
      (node (ref "IC1") (pin "5") (pinfunction "VBAT_5") (pintype "bidirectional"))
      (node (ref "IC2") (pin "3") (pinfunction "IN_3") (pintype "input"))
      (node (ref "IC3") (pin "16") (pinfunction "VCCIO_16") (pintype "power_in"))
      (node (ref "IC3") (pin "36") (pinfunction "VCCIO_36") (pintype "power_in"))
      (node (ref "IC3") (pin "44") (pinfunction "VREGIN_44") (pintype "power_in"))
      (node (ref "IC3") (pin "50") (pinfunction "VCCIO_50") (pintype "power_in"))
      (node (ref "IC4") (pin "2") (pinfunction "OUT_2") (pintype "passive"))
      (node (ref "IC4") (pin "4") (pinfunction "OUT_4") (pintype "bidirectional"))
      (node (ref "IC5") (pin "1") (pinfunction "VCA_1") (pintype "bidirectional"))
      (node (ref "IC5") (pin "3") (pinfunction "2DIR_3") (pintype "bidirectional"))
      (node (ref "IC8") (pin "1") (pinfunction "VCA_1") (pintype "bidirectional"))
      (node (ref "IC8") (pin "3") (pinfunction "2DIR_3") (pintype "bidirectional"))
      (node (ref "IC9") (pin "10") (pinfunction "OE_10") (pintype "input"))
      (node (ref "IC9") (pin "19") (pinfunction "VCCB_19") (pintype "power_in"))
      (node (ref "L1") (pin "1") (pinfunction "1_1") (pintype "passive"))
      (node (ref "L3") (pin "P$2") (pinfunction "2_P$2") (pintype "passive"))
      (node (ref "L4") (pin "P$2") (pinfunction "2_P$2") (pintype "passive"))
      (node (ref "LED2") (pin "2") (pinfunction "+_2") (pintype "passive"))
      (node (ref "R1") (pin "2") (pinfunction "2_2") (pintype "passive"))
      (node (ref "R13") (pin "1") (pinfunction "1_1") (pintype "passive"))
      (node (ref "R2") (pin "1") (pinfunction "1_1") (pintype "passive"))
      (node (ref "R42") (pin "1") (pinfunction "1_1") (pintype "passive"))
    )
    (net (code "3") (name "3V3_FEM") (class "Default")
      (node (ref "C16") (pin "1") (pinfunction "1_1") (pintype "passive"))
      (node (ref "C17") (pin "1") (pinfunction "1_1") (pintype "passive"))
      (node (ref "C4") (pin "2") (pinfunction "2_2") (pintype "passive"))
      (node (ref "C5") (pin "1") (pinfunction "1_1") (pintype "passive"))
      (node (ref "IC1") (pin "25") (pinfunction "VBAT_FEM_25") (pintype "bidirectional"))
      (node (ref "IC1") (pin "26") (pinfunction "VBAT_FEM_26") (pintype "bidirectional"))
      (node (ref "IC1") (pin "27") (pinfunction "VBAT_FEM_27") (pintype "bidirectional"))
      (node (ref "L1") (pin "2") (pinfunction "2_2") (pintype "passive"))
    )
    (net (code "4") (name "ADC0") (class "Default")
      (node (ref "IC1") (pin "59") (pinfunction "ADC0/GPIO1_59") (pintype "bidirectional"))
      (node (ref "R16") (pin "1") (pinfunction "1_1") (pintype "passive"))
    )
    (net (code "5") (name "ADC1") (class "Default")
      (node (ref "IC1") (pin "56") (pinfunction "ADC1/GPIO2_56") (pintype "bidirectional"))
      (node (ref "R17") (pin "1") (pinfunction "1_1") (pintype "passive"))
    )
    (net (code "6") (name "D+") (class "Default")
      (node (ref "CON1") (pin "3") (pinfunction "D+_3") (pintype "passive"))
      (node (ref "IC6") (pin "3") (pinfunction "I/O2_3") (pintype "bidirectional"))
      (node (ref "IC6") (pin "4") (pinfunction "I/O2_4") (pintype "bidirectional"))
      (node (ref "R10") (pin "1") (pinfunction "1_1") (pintype "passive"))
      (node (ref "TP7") (pin "P$1") (pinfunction "TP_P$1") (pintype "passive"))
    )
    (net (code "7") (name "D-") (class "Default")
      (node (ref "CON1") (pin "2") (pinfunction "D-_2") (pintype "passive"))
      (node (ref "IC6") (pin "1") (pinfunction "I/O1_1") (pintype "bidirectional"))
      (node (ref "IC6") (pin "6") (pinfunction "I/O1_6") (pintype "bidirectional"))
      (node (ref "R11") (pin "2") (pinfunction "2_2") (pintype "passive"))
      (node (ref "TP8") (pin "P$1") (pinfunction "TP_P$1") (pintype "passive"))
    )
    (net (code "8") (name "FTDI_1V8_VCORE") (class "Default")
      (node (ref "C13") (pin "1") (pinfunction "1_1") (pintype "passive"))
      (node (ref "C32") (pin "2") (pinfunction "2_2") (pintype "passive"))
      (node (ref "C33") (pin "2") (pinfunction "2_2") (pintype "passive"))
      (node (ref "C34") (pin "2") (pinfunction "2_2") (pintype "passive"))
      (node (ref "IC3") (pin "2") (pinfunction "VCORE_2") (pintype "power_in"))
      (node (ref "IC3") (pin "31") (pinfunction "VCORE_31") (pintype "power_in"))
      (node (ref "IC3") (pin "43") (pinfunction "VREGOUT_43") (pintype "power_in"))
    )
    (net (code "9") (name "GND") (class "Default")
      (node (ref "C0N2") (pin "2") (pinfunction "1_2") (pintype "passive"))
      (node (ref "C1") (pin "1") (pinfunction "1_1") (pintype "passive"))
      (node (ref "C10") (pin "1") (pinfunction "1_1") (pintype "passive"))
      (node (ref "C11") (pin "2") (pinfunction "2_2") (pintype "passive"))
      (node (ref "C12") (pin "2") (pinfunction "2_2") (pintype "passive"))
      (node (ref "C13") (pin "2") (pinfunction "2_2") (pintype "passive"))
      (node (ref "C14") (pin "1") (pinfunction "1_1") (pintype "passive"))
      (node (ref "C15") (pin "2") (pinfunction "2_2") (pintype "passive"))
      (node (ref "C16") (pin "2") (pinfunction "2_2") (pintype "passive"))
      (node (ref "C17") (pin "2") (pinfunction "2_2") (pintype "passive"))
      (node (ref "C18") (pin "2") (pinfunction "2_2") (pintype "passive"))
      (node (ref "C19") (pin "2") (pinfunction "2_2") (pintype "passive"))
      (node (ref "C2") (pin "2") (pinfunction "2_2") (pintype "passive"))
      (node (ref "C20") (pin "1") (pinfunction "1_1") (pintype "passive"))
      (node (ref "C21") (pin "2") (pinfunction "2_2") (pintype "passive"))
      (node (ref "C22") (pin "1") (pinfunction "1_1") (pintype "passive"))
      (node (ref "C23") (pin "2") (pinfunction "2_2") (pintype "passive"))
      (node (ref "C24") (pin "1") (pinfunction "1_1") (pintype "passive"))
      (node (ref "C25") (pin "1") (pinfunction "1_1") (pintype "passive"))
      (node (ref "C26") (pin "1") (pinfunction "1_1") (pintype "passive"))
      (node (ref "C27") (pin "1") (pinfunction "1_1") (pintype "passive"))
      (node (ref "C28") (pin "1") (pinfunction "1_1") (pintype "passive"))
      (node (ref "C29") (pin "1") (pinfunction "1_1") (pintype "passive"))
      (node (ref "C3") (pin "2") (pinfunction "2_2") (pintype "passive"))
      (node (ref "C30") (pin "1") (pinfunction "1_1") (pintype "passive"))
      (node (ref "C31") (pin "1") (pinfunction "1_1") (pintype "passive"))
      (node (ref "C32") (pin "1") (pinfunction "1_1") (pintype "passive"))
      (node (ref "C33") (pin "1") (pinfunction "1_1") (pintype "passive"))
      (node (ref "C34") (pin "1") (pinfunction "1_1") (pintype "passive"))
      (node (ref "C35") (pin "1") (pinfunction "1_1") (pintype "passive"))
      (node (ref "C36") (pin "1") (pinfunction "1_1") (pintype "passive"))
      (node (ref "C37") (pin "1") (pinfunction "1_1") (pintype "passive"))
      (node (ref "C38") (pin "1") (pinfunction "1_1") (pintype "passive"))
      (node (ref "C39") (pin "1") (pinfunction "1_1") (pintype "passive"))
      (node (ref "C4") (pin "1") (pinfunction "1_1") (pintype "passive"))
      (node (ref "C40") (pin "1") (pinfunction "1_1") (pintype "passive"))
      (node (ref "C41") (pin "P$2") (pinfunction "2_P$2") (pintype "passive"))
      (node (ref "C46") (pin "1") (pinfunction "1_1") (pintype "passive"))
      (node (ref "C47") (pin "1") (pinfunction "1_1") (pintype "passive"))
      (node (ref "C5") (pin "2") (pinfunction "2_2") (pintype "passive"))
      (node (ref "C50") (pin "1") (pinfunction "1_1") (pintype "passive"))
      (node (ref "C51") (pin "1") (pinfunction "1_1") (pintype "passive"))
      (node (ref "C55") (pin "1") (pinfunction "1_1") (pintype "passive"))
      (node (ref "C56") (pin "1") (pinfunction "1_1") (pintype "passive"))
      (node (ref "C6") (pin "1") (pinfunction "1_1") (pintype "passive"))
      (node (ref "C7") (pin "2") (pinfunction "2_2") (pintype "passive"))
      (node (ref "C8") (pin "1") (pinfunction "1_1") (pintype "passive"))
      (node (ref "C9") (pin "2") (pinfunction "2_2") (pintype "passive"))
      (node (ref "CON1") (pin "5") (pinfunction "GND_5") (pintype "passive"))
      (node (ref "CON1") (pin "SHELL") (pinfunction "SHIELD_SHELL") (pintype "passive"))
      (node (ref "CON1") (pin "SHELL1") (pinfunction "SHIELD_SHELL1") (pintype "passive"))
      (node (ref "CON1") (pin "SHELL2") (pinfunction "SHIELD_SHELL2") (pintype "passive"))
      (node (ref "CON1") (pin "SHELL3") (pinfunction "SHIELD_SHELL3") (pintype "passive"))
      (node (ref "CON3") (pin "C5") (pinfunction "GND_C5") (pintype "bidirectional"))
      (node (ref "CON3") (pin "S1") (pinfunction "SHIELD_S1") (pintype "bidirectional"))
      (node (ref "CON3") (pin "S2") (pinfunction "SHIELD_S2") (pintype "bidirectional"))
      (node (ref "CON3") (pin "S3") (pinfunction "SHIELD_S3") (pintype "bidirectional"))
      (node (ref "CON3") (pin "S4") (pinfunction "SHIELD_S4") (pintype "bidirectional"))
      (node (ref "CON3") (pin "S5") (pinfunction "SHIELD_S5") (pintype "bidirectional"))
      (node (ref "CON3") (pin "S6") (pinfunction "SHIELD_S6") (pintype "bidirectional"))
      (node (ref "CON4") (pin "2") (pinfunction "2_2") (pintype "passive"))
      (node (ref "CON4") (pin "3") (pinfunction "2_3") (pintype "passive"))
      (node (ref "CON5") (pin "2") (pinfunction "2_2") (pintype "passive"))
      (node (ref "CON5") (pin "3") (pinfunction "2_3") (pintype "passive"))
      (node (ref "D3") (pin "2") (pinfunction "2_2") (pintype "passive"))
      (node (ref "D4") (pin "2") (pinfunction "2_2") (pintype "passive"))
      (node (ref "IC1") (pin "1") (pinfunction "GND_1") (pintype "bidirectional"))
      (node (ref "IC1") (pin "100") (pinfunction "GND_100") (pintype "bidirectional"))
      (node (ref "IC1") (pin "101") (pinfunction "GND_101") (pintype "bidirectional"))
      (node (ref "IC1") (pin "102") (pinfunction "GND_102") (pintype "bidirectional"))
      (node (ref "IC1") (pin "103") (pinfunction "GND_103") (pintype "bidirectional"))
      (node (ref "IC1") (pin "104") (pinfunction "GND_104") (pintype "bidirectional"))
      (node (ref "IC1") (pin "2") (pinfunction "GND_2") (pintype "bidirectional"))
      (node (ref "IC1") (pin "28") (pinfunction "GND_28") (pintype "bidirectional"))
      (node (ref "IC1") (pin "29") (pinfunction "GND_29") (pintype "bidirectional"))
      (node (ref "IC1") (pin "30") (pinfunction "GND_30") (pintype "bidirectional"))
      (node (ref "IC1") (pin "31") (pinfunction "GND_31") (pintype "bidirectional"))
      (node (ref "IC1") (pin "32") (pinfunction "GND_32") (pintype "bidirectional"))
      (node (ref "IC1") (pin "33") (pinfunction "GND_33") (pintype "bidirectional"))
      (node (ref "IC1") (pin "34") (pinfunction "GND_34") (pintype "bidirectional"))
      (node (ref "IC1") (pin "35") (pinfunction "GND_35") (pintype "bidirectional"))
      (node (ref "IC1") (pin "36") (pinfunction "GND_36") (pintype "bidirectional"))
      (node (ref "IC1") (pin "37") (pinfunction "GND_37") (pintype "bidirectional"))
      (node (ref "IC1") (pin "38") (pinfunction "GND_38") (pintype "bidirectional"))
      (node (ref "IC1") (pin "40") (pinfunction "GND_40") (pintype "bidirectional"))
      (node (ref "IC1") (pin "41") (pinfunction "GND_41") (pintype "bidirectional"))
      (node (ref "IC1") (pin "42") (pinfunction "GND_42") (pintype "bidirectional"))
      (node (ref "IC1") (pin "45") (pinfunction "GND_45") (pintype "bidirectional"))
      (node (ref "IC1") (pin "46") (pinfunction "GND_46") (pintype "bidirectional"))
      (node (ref "IC1") (pin "51") (pinfunction "GND_51") (pintype "bidirectional"))
      (node (ref "IC1") (pin "52") (pinfunction "GND_52") (pintype "bidirectional"))
      (node (ref "IC1") (pin "57") (pinfunction "GND_57") (pintype "bidirectional"))
      (node (ref "IC1") (pin "86") (pinfunction "GND_86") (pintype "bidirectional"))
      (node (ref "IC1") (pin "88") (pinfunction "GND_88") (pintype "bidirectional"))
      (node (ref "IC1") (pin "90") (pinfunction "GND_90") (pintype "bidirectional"))
      (node (ref "IC1") (pin "92") (pinfunction "GND_92") (pintype "bidirectional"))
      (node (ref "IC1") (pin "93") (pinfunction "GND_93") (pintype "bidirectional"))
      (node (ref "IC1") (pin "94") (pinfunction "GND_94") (pintype "bidirectional"))
      (node (ref "IC1") (pin "95") (pinfunction "GND_95") (pintype "bidirectional"))
      (node (ref "IC1") (pin "96") (pinfunction "GND_96") (pintype "bidirectional"))
      (node (ref "IC1") (pin "97") (pinfunction "GND_97") (pintype "bidirectional"))
      (node (ref "IC1") (pin "98") (pinfunction "GND_98") (pintype "bidirectional"))
      (node (ref "IC1") (pin "99") (pinfunction "GND_99") (pintype "bidirectional"))
      (node (ref "IC2") (pin "1") (pinfunction "ADJ_1") (pintype "input"))
      (node (ref "IC3") (pin "10") (pinfunction "TEST_10") (pintype "input"))
      (node (ref "IC3") (pin "21") (pinfunction "GND_21") (pintype "power_in"))
      (node (ref "IC3") (pin "41") (pinfunction "GND_41") (pintype "power_in"))
      (node (ref "IC3") (pin "45") (pinfunction "GND_45") (pintype "power_in"))
      (node (ref "IC3") (pin "P$1") (pinfunction "GND_P$1") (pintype "power_in"))
      (node (ref "IC3") (pin "P$2") (pinfunction "GND_P$2") (pintype "power_in"))
      (node (ref "IC3") (pin "P$3") (pinfunction "GND_P$3") (pintype "power_in"))
      (node (ref "IC4") (pin "1") (pinfunction "ADJ_1") (pintype "input"))
      (node (ref "IC5") (pin "2") (pinfunction "1DIR_2") (pintype "bidirectional"))
      (node (ref "IC5") (pin "8") (pinfunction "GND_8") (pintype "bidirectional"))
      (node (ref "IC5") (pin "9") (pinfunction "GND_9") (pintype "bidirectional"))
      (node (ref "IC6") (pin "2") (pinfunction "GND_2") (pintype "power_in"))
      (node (ref "IC7") (pin "2") (pinfunction "VSS_2") (pintype "bidirectional"))
      (node (ref "IC8") (pin "2") (pinfunction "1DIR_2") (pintype "bidirectional"))
      (node (ref "IC8") (pin "8") (pinfunction "GND_8") (pintype "bidirectional"))
      (node (ref "IC8") (pin "9") (pinfunction "GND_9") (pintype "bidirectional"))
      (node (ref "IC9") (pin "11") (pinfunction "GND_11") (pintype "power_in"))
      (node (ref "LED1") (pin "1") (pinfunction "-_1") (pintype "passive"))
      (node (ref "MS1") (pin "4") (pinfunction "GND_4") (pintype "power_in"))
      (node (ref "Q1") (pin "2") (pinfunction "GND_2") (pintype "passive"))
      (node (ref "Q1") (pin "4") (pinfunction "GND_4") (pintype "passive"))
      (node (ref "R12") (pin "1") (pinfunction "1_1") (pintype "passive"))
      (node (ref "R20") (pin "2") (pinfunction "2_2") (pintype "passive"))
      (node (ref "R43") (pin "2") (pinfunction "2_2") (pintype "passive"))
      (node (ref "R6") (pin "1") (pinfunction "1_1") (pintype "passive"))
      (node (ref "R7") (pin "2") (pinfunction "2_2") (pintype "passive"))
      (node (ref "R8") (pin "2") (pinfunction "2_2") (pintype "passive"))
      (node (ref "S1") (pin "3") (pinfunction "3_3") (pintype "passive"))
      (node (ref "S1") (pin "4") (pinfunction "4_4") (pintype "passive"))
      (node (ref "S1") (pin "5") (pinfunction "3_5") (pintype "passive"))
      (node (ref "S1") (pin "6") (pinfunction "4_6") (pintype "passive"))
      (node (ref "T1") (pin "S") (pinfunction "S_S") (pintype "passive"))
      (node (ref "TP10") (pin "P$1") (pinfunction "TP_P$1") (pintype "passive"))
      (node (ref "TP11") (pin "P$1") (pinfunction "TP_P$1") (pintype "passive"))
      (node (ref "TP12") (pin "P$1") (pinfunction "TP_P$1") (pintype "passive"))
      (node (ref "TP6") (pin "P$1") (pinfunction "TP_P$1") (pintype "passive"))
    )
    (net (code "10") (name "GNSS_RX") (class "Default")
      (node (ref "C47") (pin "2") (pinfunction "2_2") (pintype "passive"))
      (node (ref "IC1") (pin "43") (pinfunction "RF_GNSS_ANT_43") (pintype "bidirectional"))
      (node (ref "R35") (pin "2") (pinfunction "2_2") (pintype "passive"))
    )
    (net (code "11") (name "GPIO_RX") (class "Default")
      (node (ref "IC5") (pin "4") (pinfunction "1A1_4") (pintype "bidirectional"))
      (node (ref "MS1") (pin "14") (pinfunction "GPIORX_14") (pintype "bidirectional"))
      (node (ref "R15") (pin "2") (pinfunction "2_2") (pintype "passive"))
    )
    (net (code "12") (name "GPIO_TX") (class "Default")
      (node (ref "IC5") (pin "6") (pinfunction "2A1_6") (pintype "bidirectional"))
      (node (ref "MS1") (pin "15") (pinfunction "GPIOTX_15") (pintype "bidirectional"))
      (node (ref "R14") (pin "2") (pinfunction "2_2") (pintype "passive"))
    )
    (net (code "13") (name "I2C_SCL") (class "Default")
      (node (ref "IC9") (pin "20") (pinfunction "B1_20") (pintype "bidirectional"))
      (node (ref "MS1") (pin "18") (pinfunction "GPIOSCL_18") (pintype "bidirectional"))
    )
    (net (code "14") (name "I2C_SDA") (class "Default")
      (node (ref "IC9") (pin "18") (pinfunction "B2_18") (pintype "bidirectional"))
      (node (ref "MS1") (pin "17") (pinfunction "GPIOSDA_17") (pintype "bidirectional"))
    )
    (net (code "15") (name "LTE_RXTX") (class "Default")
      (node (ref "C46") (pin "2") (pinfunction "2_2") (pintype "passive"))
      (node (ref "IC1") (pin "39") (pinfunction "RF_RXTX_39") (pintype "bidirectional"))
      (node (ref "R34") (pin "2") (pinfunction "2_2") (pintype "passive"))
    )
    (net (code "16") (name "M_I2C_SCL") (class "Default")
      (node (ref "IC1") (pin "15") (pinfunction "I2C0_SCL/GPIO43_15") (pintype "bidirectional"))
      (node (ref "IC9") (pin "1") (pinfunction "A1_1") (pintype "bidirectional"))
    )
    (net (code "17") (name "M_I2C_SDA") (class "Default")
      (node (ref "IC1") (pin "17") (pinfunction "I2C0_SDA/GPIO42_17") (pintype "bidirectional"))
      (node (ref "IC9") (pin "3") (pinfunction "A2_3") (pintype "bidirectional"))
    )
    (net (code "18") (name "M_SPI_CLK") (class "Default")
      (node (ref "IC1") (pin "76") (pinfunction "SPIM1_CLK/GPIO41_76") (pintype "bidirectional"))
      (node (ref "IC9") (pin "5") (pinfunction "A4_5") (pintype "bidirectional"))
    )
    (net (code "19") (name "M_SPI_CS") (class "Default")
      (node (ref "IC1") (pin "81") (pinfunction "SPIM1_EN/GPIO40_81") (pintype "bidirectional"))
      (node (ref "IC9") (pin "4") (pinfunction "A3_4") (pintype "bidirectional"))
    )
    (net (code "20") (name "M_SPI_MISO") (class "Default")
      (node (ref "IC1") (pin "74") (pinfunction "SPIM1_MISO/GPIO39_74") (pintype "bidirectional"))
      (node (ref "IC9") (pin "7") (pinfunction "A6_7") (pintype "bidirectional"))
    )
    (net (code "21") (name "M_SPI_MOSI") (class "Default")
      (node (ref "IC1") (pin "83") (pinfunction "SPIM1_MOSI/GPIO38_83") (pintype "bidirectional"))
      (node (ref "IC9") (pin "6") (pinfunction "A5_6") (pintype "bidirectional"))
    )
    (net (code "22") (name "M_WAKEUP") (class "Default")
      (node (ref "C55") (pin "2") (pinfunction "2_2") (pintype "passive"))
      (node (ref "IC1") (pin "7") (pinfunction "WAKEUP_7") (pintype "bidirectional"))
      (node (ref "IC9") (pin "8") (pinfunction "A7_8") (pintype "bidirectional"))
    )
    (net (code "23") (name "M_{slash}RESET") (class "Default")
      (node (ref "C56") (pin "2") (pinfunction "2_2") (pintype "passive"))
      (node (ref "IC1") (pin "9") (pinfunction "/RESET_9") (pintype "bidirectional"))
      (node (ref "IC9") (pin "9") (pinfunction "A8_9") (pintype "bidirectional"))
      (node (ref "S1") (pin "1") (pinfunction "1_1") (pintype "passive"))
      (node (ref "S1") (pin "2") (pinfunction "2_2") (pintype "passive"))
      (node (ref "TP5") (pin "P$1") (pinfunction "TP_P$1") (pintype "passive"))
    )
    (net (code "24") (name "Net-(C48-Pad1)") (class "Default")
      (node (ref "C48") (pin "1") (pinfunction "1_1") (pintype "passive"))
      (node (ref "CON4") (pin "1") (pinfunction "1_1") (pintype "passive"))
      (node (ref "D3") (pin "1") (pinfunction "1_1") (pintype "passive"))
    )
    (net (code "25") (name "Net-(C48-Pad2)") (class "Default")
      (node (ref "C48") (pin "2") (pinfunction "2_2") (pintype "passive"))
      (node (ref "C50") (pin "2") (pinfunction "2_2") (pintype "passive"))
      (node (ref "R34") (pin "1") (pinfunction "1_1") (pintype "passive"))
    )
    (net (code "26") (name "Net-(C49-Pad1)") (class "Default")
      (node (ref "C49") (pin "1") (pinfunction "1_1") (pintype "passive"))
      (node (ref "CON5") (pin "1") (pinfunction "1_1") (pintype "passive"))
      (node (ref "D4") (pin "1") (pinfunction "1_1") (pintype "passive"))
    )
    (net (code "27") (name "Net-(C49-Pad2)") (class "Default")
      (node (ref "C49") (pin "2") (pinfunction "2_2") (pintype "passive"))
      (node (ref "C51") (pin "2") (pinfunction "2_2") (pintype "passive"))
      (node (ref "R35") (pin "1") (pinfunction "1_1") (pintype "passive"))
    )
    (net (code "28") (name "Net-(CON1-VBUS)") (class "Default")
      (node (ref "CON1") (pin "1") (pinfunction "VBUS_1") (pintype "passive"))
      (node (ref "F1") (pin "1") (pinfunction "1_1") (pintype "passive"))
      (node (ref "TP9") (pin "P$1") (pinfunction "TP_P$1") (pintype "passive"))
    )
    (net (code "29") (name "Net-(D2-C)") (class "Default")
      (node (ref "C20") (pin "2") (pinfunction "2_2") (pintype "passive"))
      (node (ref "D2") (pin "3") (pinfunction "C_3") (pintype "passive"))
      (node (ref "D7") (pin "K") (pinfunction "C_K") (pintype "passive"))
      (node (ref "D8") (pin "K") (pinfunction "C_K") (pintype "passive"))
      (node (ref "IC4") (pin "3") (pinfunction "IN_3") (pintype "input"))
    )
    (net (code "30") (name "Net-(D6-A)") (class "Default")
      (node (ref "D6") (pin "2") (pinfunction "A_2") (pintype "passive"))
      (node (ref "MS1") (pin "20") (pinfunction "GPIO6_20") (pintype "bidirectional"))
    )
    (net (code "31") (name "Net-(IC3-ADBUS0)") (class "Default")
      (node (ref "IC3") (pin "12") (pinfunction "ADBUS0_12") (pintype "bidirectional"))
      (node (ref "R14") (pin "1") (pinfunction "1_1") (pintype "passive"))
    )
    (net (code "32") (name "Net-(IC3-ADBUS1)") (class "Default")
      (node (ref "IC3") (pin "13") (pinfunction "ADBUS1_13") (pintype "bidirectional"))
      (node (ref "R15") (pin "1") (pinfunction "1_1") (pintype "passive"))
    )
    (net (code "33") (name "Net-(IC3-BDBUS0)") (class "Default")
      (node (ref "IC3") (pin "22") (pinfunction "BDBUS0_22") (pintype "bidirectional"))
      (node (ref "R18") (pin "1") (pinfunction "1_1") (pintype "passive"))
    )
    (net (code "34") (name "Net-(IC3-BDBUS1)") (class "Default")
      (node (ref "IC3") (pin "23") (pinfunction "BDBUS1_23") (pintype "bidirectional"))
      (node (ref "R19") (pin "1") (pinfunction "1_1") (pintype "passive"))
    )
    (net (code "35") (name "Net-(IC3-CDBUS0)") (class "Default")
      (node (ref "IC3") (pin "32") (pinfunction "CDBUS0_32") (pintype "bidirectional"))
      (node (ref "R22") (pin "1") (pinfunction "1_1") (pintype "passive"))
    )
    (net (code "36") (name "Net-(IC3-CDBUS1)") (class "Default")
      (node (ref "IC3") (pin "33") (pinfunction "CDBUS1_33") (pintype "bidirectional"))
      (node (ref "R23") (pin "1") (pinfunction "1_1") (pintype "passive"))
    )
    (net (code "37") (name "Net-(IC3-CDBUS2)") (class "Default")
      (node (ref "IC3") (pin "34") (pinfunction "CDBUS2_34") (pintype "bidirectional"))
      (node (ref "R24") (pin "1") (pinfunction "1_1") (pintype "passive"))
    )
    (net (code "38") (name "Net-(IC3-CDBUS3)") (class "Default")
      (node (ref "IC3") (pin "35") (pinfunction "CDBUS3_35") (pintype "bidirectional"))
      (node (ref "R25") (pin "1") (pinfunction "1_1") (pintype "passive"))
    )
    (net (code "39") (name "Net-(IC3-DM)") (class "Default")
      (node (ref "C8") (pin "2") (pinfunction "2_2") (pintype "passive"))
      (node (ref "IC3") (pin "7") (pinfunction "DM_7") (pintype "input"))
      (node (ref "R11") (pin "1") (pinfunction "1_1") (pintype "passive"))
    )
    (net (code "40") (name "Net-(IC3-DP)") (class "Default")
      (node (ref "C10") (pin "2") (pinfunction "2_2") (pintype "passive"))
      (node (ref "IC3") (pin "8") (pinfunction "DP_8") (pintype "input"))
      (node (ref "R10") (pin "2") (pinfunction "2_2") (pintype "passive"))
    )
    (net (code "41") (name "Net-(IC3-OSCI)") (class "Default")
      (node (ref "C24") (pin "2") (pinfunction "2_2") (pintype "passive"))
      (node (ref "IC3") (pin "3") (pinfunction "OSCI_3") (pintype "input"))
      (node (ref "Q1") (pin "1") (pinfunction "1_1") (pintype "passive"))
    )
    (net (code "42") (name "Net-(IC3-OSCO)") (class "Default")
      (node (ref "C26") (pin "2") (pinfunction "2_2") (pintype "passive"))
      (node (ref "IC3") (pin "4") (pinfunction "OSCO_4") (pintype "output"))
      (node (ref "Q1") (pin "3") (pinfunction "2_3") (pintype "passive"))
    )
    (net (code "43") (name "Net-(IC3-REF)") (class "Default")
      (node (ref "IC3") (pin "6") (pinfunction "REF_6") (pintype "input"))
      (node (ref "R12") (pin "2") (pinfunction "2_2") (pintype "passive"))
    )
    (net (code "44") (name "Net-(IC3-RESET#)") (class "Default")
      (node (ref "C28") (pin "2") (pinfunction "2_2") (pintype "passive"))
      (node (ref "IC3") (pin "11") (pinfunction "RESET#_11") (pintype "input"))
      (node (ref "R13") (pin "2") (pinfunction "2_2") (pintype "passive"))
    )
    (net (code "45") (name "Net-(IC3-VPHY)") (class "Default")
      (node (ref "C11") (pin "1") (pinfunction "1_1") (pintype "passive"))
      (node (ref "C27") (pin "2") (pinfunction "2_2") (pintype "passive"))
      (node (ref "IC3") (pin "5") (pinfunction "VPHY_5") (pintype "power_in"))
      (node (ref "L4") (pin "P$1") (pinfunction "1_P$1") (pintype "passive"))
    )
    (net (code "46") (name "Net-(IC3-VPLL)") (class "Default")
      (node (ref "C12") (pin "1") (pinfunction "1_1") (pintype "passive"))
      (node (ref "C31") (pin "2") (pinfunction "2_2") (pintype "passive"))
      (node (ref "IC3") (pin "9") (pinfunction "VPLL_9") (pintype "power_in"))
      (node (ref "L3") (pin "P$1") (pinfunction "1_P$1") (pintype "passive"))
    )
    (net (code "47") (name "Net-(IC5-1~{OE})") (class "Default")
      (node (ref "IC5") (pin "14") (pinfunction "2~{OE}_14") (pintype "bidirectional"))
      (node (ref "IC5") (pin "15") (pinfunction "1~{OE}_15") (pintype "bidirectional"))
      (node (ref "R7") (pin "1") (pinfunction "1_1") (pintype "passive"))
    )
    (net (code "48") (name "Net-(IC6-VDD)") (class "Default")
      (node (ref "F1") (pin "2") (pinfunction "2_2") (pintype "passive"))
      (node (ref "IC6") (pin "5") (pinfunction "VDD_5") (pintype "power_in"))
      (node (ref "L2") (pin "P$2") (pinfunction "2_P$2") (pintype "passive"))
    )
    (net (code "49") (name "Net-(IC7-PROG)") (class "Default")
      (node (ref "IC7") (pin "5") (pinfunction "PROG_5") (pintype "bidirectional"))
      (node (ref "R6") (pin "2") (pinfunction "2_2") (pintype "passive"))
    )
    (net (code "50") (name "Net-(IC7-STAT)") (class "Default")
      (node (ref "IC7") (pin "1") (pinfunction "STAT_1") (pintype "bidirectional"))
      (node (ref "R5") (pin "2") (pinfunction "2_2") (pintype "passive"))
    )
    (net (code "51") (name "Net-(IC8-1~{OE})") (class "Default")
      (node (ref "IC8") (pin "14") (pinfunction "2~{OE}_14") (pintype "bidirectional"))
      (node (ref "IC8") (pin "15") (pinfunction "1~{OE}_15") (pintype "bidirectional"))
      (node (ref "R20") (pin "1") (pinfunction "1_1") (pintype "passive"))
    )
    (net (code "52") (name "Net-(L2-1)") (class "Default")
      (node (ref "D5") (pin "A") (pinfunction "A_A") (pintype "passive"))
      (node (ref "L2") (pin "P$1") (pinfunction "1_P$1") (pintype "passive"))
    )
    (net (code "53") (name "Net-(LED1-+)") (class "Default")
      (node (ref "LED1") (pin "2") (pinfunction "+_2") (pintype "passive"))
      (node (ref "R1") (pin "1") (pinfunction "1_1") (pintype "passive"))
    )
    (net (code "54") (name "Net-(LED2--)") (class "Default")
      (node (ref "LED2") (pin "1") (pinfunction "-_1") (pintype "passive"))
      (node (ref "R3") (pin "1") (pinfunction "1_1") (pintype "passive"))
    )
    (net (code "55") (name "Net-(LED3--)") (class "Default")
      (node (ref "LED3") (pin "1") (pinfunction "-_1") (pintype "passive"))
      (node (ref "R5") (pin "1") (pinfunction "1_1") (pintype "passive"))
    )
    (net (code "56") (name "Net-(MS1-3V)") (class "Default")
      (node (ref "MS1") (pin "2") (pinfunction "3V_2") (pintype "power_in"))
      (node (ref "R2") (pin "2") (pinfunction "2_2") (pintype "passive"))
    )
    (net (code "57") (name "Net-(MS1-GPIOA0)") (class "Default")
      (node (ref "MS1") (pin "5") (pinfunction "GPIOA0_5") (pintype "bidirectional"))
      (node (ref "R16") (pin "2") (pinfunction "2_2") (pintype "passive"))
    )
    (net (code "58") (name "Net-(MS1-GPIOA1)") (class "Default")
      (node (ref "MS1") (pin "6") (pinfunction "GPIOA1_6") (pintype "bidirectional"))
      (node (ref "R17") (pin "2") (pinfunction "2_2") (pintype "passive"))
    )
    (net (code "59") (name "Net-(MS1-USB)") (class "Default")
      (node (ref "MS1") (pin "26") (pinfunction "USB_26") (pintype "power_in"))
      (node (ref "R4") (pin "1") (pinfunction "1_1") (pintype "passive"))
    )
    (net (code "60") (name "Net-(R3-Pad2)") (class "Default")
      (node (ref "R3") (pin "2") (pinfunction "2_2") (pintype "passive"))
      (node (ref "T1") (pin "D") (pinfunction "D_D") (pintype "passive"))
    )
    (net (code "61") (name "Net-(R8-Pad1)") (class "Default")
      (node (ref "R8") (pin "1") (pinfunction "1_1") (pintype "passive"))
      (node (ref "R9") (pin "2") (pinfunction "2_2") (pintype "passive"))
      (node (ref "T1") (pin "G") (pinfunction "G_G") (pintype "passive"))
    )
    (net (code "62") (name "Net-(R42-Pad2)") (class "Default")
      (node (ref "R42") (pin "2") (pinfunction "2_2") (pintype "passive"))
      (node (ref "S2") (pin "1") (pinfunction "1_1") (pintype "passive"))
      (node (ref "S2") (pin "2") (pinfunction "2_2") (pintype "passive"))
    )
    (net (code "63") (name "SIM_CLK") (class "Default")
      (node (ref "CON3") (pin "C3") (pinfunction "CLK_C3") (pintype "bidirectional"))
      (node (ref "IC1") (pin "75") (pinfunction "SIMCLK_75") (pintype "bidirectional"))
    )
    (net (code "64") (name "SIM_IO") (class "Default")
      (node (ref "CON3") (pin "C7") (pinfunction "I/O_C7") (pintype "bidirectional"))
      (node (ref "IC1") (pin "79") (pinfunction "SIMIO_79") (pintype "bidirectional"))
    )
    (net (code "65") (name "SIM_RST") (class "Default")
      (node (ref "CON3") (pin "C2") (pinfunction "RST_C2") (pintype "bidirectional"))
      (node (ref "IC1") (pin "77") (pinfunction "SIMRST_77") (pintype "bidirectional"))
    )
    (net (code "66") (name "SPI_CLK") (class "Default")
      (node (ref "IC9") (pin "16") (pinfunction "B4_16") (pintype "bidirectional"))
      (node (ref "MS1") (pin "11") (pinfunction "GPIOSCK_11") (pintype "bidirectional"))
    )
    (net (code "67") (name "SPI_CS") (class "Default")
      (node (ref "IC9") (pin "17") (pinfunction "B3_17") (pintype "bidirectional"))
      (node (ref "MS1") (pin "10") (pinfunction "GPIOA5_10") (pintype "bidirectional"))
    )
    (net (code "68") (name "SPI_MISO") (class "Default")
      (node (ref "IC9") (pin "14") (pinfunction "B6_14") (pintype "bidirectional"))
      (node (ref "MS1") (pin "13") (pinfunction "GPIOMISO_13") (pintype "bidirectional"))
    )
    (net (code "69") (name "SPI_MOSI") (class "Default")
      (node (ref "IC9") (pin "15") (pinfunction "B5_15") (pintype "bidirectional"))
      (node (ref "MS1") (pin "12") (pinfunction "GPIOMOSI_12") (pintype "bidirectional"))
    )
    (net (code "70") (name "STATUS") (class "Default")
      (node (ref "IC1") (pin "58") (pinfunction "STATUS_58") (pintype "bidirectional"))
      (node (ref "R9") (pin "1") (pinfunction "1_1") (pintype "passive"))
    )
    (net (code "71") (name "U1_3V3_RX") (class "Default")
      (node (ref "IC5") (pin "5") (pinfunction "1A2_5") (pintype "bidirectional"))
      (node (ref "R19") (pin "2") (pinfunction "2_2") (pintype "passive"))
    )
    (net (code "72") (name "U1_3V3_TX") (class "Default")
      (node (ref "IC5") (pin "7") (pinfunction "2A2_7") (pintype "bidirectional"))
      (node (ref "R18") (pin "2") (pinfunction "2_2") (pintype "passive"))
    )
    (net (code "73") (name "U2_3V3_CTS") (class "Default")
      (node (ref "IC8") (pin "4") (pinfunction "1A1_4") (pintype "bidirectional"))
      (node (ref "R25") (pin "2") (pinfunction "2_2") (pintype "passive"))
    )
    (net (code "74") (name "U2_3V3_RTS") (class "Default")
      (node (ref "IC8") (pin "6") (pinfunction "2A1_6") (pintype "bidirectional"))
      (node (ref "R24") (pin "2") (pinfunction "2_2") (pintype "passive"))
    )
    (net (code "75") (name "U2_3V3_RX") (class "Default")
      (node (ref "IC8") (pin "5") (pinfunction "1A2_5") (pintype "bidirectional"))
      (node (ref "R23") (pin "2") (pinfunction "2_2") (pintype "passive"))
    )
    (net (code "76") (name "U2_3V3_TX") (class "Default")
      (node (ref "IC8") (pin "7") (pinfunction "2A2_7") (pintype "bidirectional"))
      (node (ref "R22") (pin "2") (pinfunction "2_2") (pintype "passive"))
    )
    (net (code "77") (name "UART0_RX") (class "Default")
      (node (ref "IC1") (pin "22") (pinfunction "UART0_RX/GPIO23_22") (pintype "bidirectional"))
      (node (ref "IC5") (pin "11") (pinfunction "2B1_11") (pintype "bidirectional"))
    )
    (net (code "78") (name "UART0_TX") (class "Default")
      (node (ref "IC1") (pin "21") (pinfunction "UART0_TX/GPIO24_21") (pintype "bidirectional"))
      (node (ref "IC5") (pin "13") (pinfunction "1B1_13") (pintype "bidirectional"))
    )
    (net (code "79") (name "UART1_CTS") (class "Default")
      (node (ref "IC1") (pin "65") (pinfunction "UART1_CTS_65") (pintype "bidirectional"))
      (node (ref "TP2") (pin "P$1") (pinfunction "TP_P$1") (pintype "passive"))
    )
    (net (code "80") (name "UART1_RTS") (class "Default")
      (node (ref "IC1") (pin "61") (pinfunction "UART1_RTS_61") (pintype "bidirectional"))
      (node (ref "TP4") (pin "P$1") (pinfunction "TP_P$1") (pintype "passive"))
    )
    (net (code "81") (name "UART1_RX") (class "Default")
      (node (ref "IC1") (pin "63") (pinfunction "UART1_RX_63") (pintype "bidirectional"))
      (node (ref "IC5") (pin "10") (pinfunction "2B2_10") (pintype "bidirectional"))
      (node (ref "TP1") (pin "P$1") (pinfunction "TP_P$1") (pintype "passive"))
    )
    (net (code "82") (name "UART1_TX") (class "Default")
      (node (ref "IC1") (pin "60") (pinfunction "UART1_TX_60") (pintype "bidirectional"))
      (node (ref "IC5") (pin "12") (pinfunction "1B2_12") (pintype "bidirectional"))
      (node (ref "TP3") (pin "P$1") (pinfunction "TP_P$1") (pintype "passive"))
    )
    (net (code "83") (name "UART2_CTS") (class "Default")
      (node (ref "IC1") (pin "53") (pinfunction "UART2_CTS_53") (pintype "bidirectional"))
      (node (ref "IC8") (pin "11") (pinfunction "2B1_11") (pintype "bidirectional"))
    )
    (net (code "84") (name "UART2_RTS") (class "Default")
      (node (ref "IC1") (pin "55") (pinfunction "UART2_RTS_55") (pintype "bidirectional"))
      (node (ref "IC8") (pin "13") (pinfunction "1B1_13") (pintype "bidirectional"))
    )
    (net (code "85") (name "UART2_RX") (class "Default")
      (node (ref "IC1") (pin "50") (pinfunction "UART2_RX_50") (pintype "bidirectional"))
      (node (ref "IC8") (pin "10") (pinfunction "2B2_10") (pintype "bidirectional"))
    )
    (net (code "86") (name "UART2_TX") (class "Default")
      (node (ref "IC1") (pin "48") (pinfunction "UART2_TX_48") (pintype "bidirectional"))
      (node (ref "IC8") (pin "12") (pinfunction "1B2_12") (pintype "bidirectional"))
    )
    (net (code "87") (name "USB_5V") (class "Default")
      (node (ref "C39") (pin "2") (pinfunction "2_2") (pintype "passive"))
      (node (ref "D5") (pin "K") (pinfunction "C_K") (pintype "passive"))
      (node (ref "D7") (pin "A") (pinfunction "A_A") (pintype "passive"))
      (node (ref "IC7") (pin "4") (pinfunction "VDD_4") (pintype "bidirectional"))
      (node (ref "LED3") (pin "2") (pinfunction "+_2") (pintype "passive"))
      (node (ref "R4") (pin "2") (pinfunction "2_2") (pintype "passive"))
    )
    (net (code "88") (name "VBAT") (class "Default")
      (node (ref "C0N2") (pin "1") (pinfunction "2_1") (pintype "passive"))
      (node (ref "C15") (pin "1") (pinfunction "1_1") (pintype "passive"))
      (node (ref "D8") (pin "A") (pinfunction "A_A") (pintype "passive"))
      (node (ref "IC7") (pin "3") (pinfunction "VBAT_3") (pintype "bidirectional"))
      (node (ref "MS1") (pin "28") (pinfunction "VBAT_28") (pintype "power_in"))
    )
    (net (code "89") (name "VCC_SIM") (class "Default")
      (node (ref "C3") (pin "1") (pinfunction "1_1") (pintype "passive"))
      (node (ref "CON3") (pin "C1") (pinfunction "VCC_C1") (pintype "bidirectional"))
      (node (ref "IC1") (pin "72") (pinfunction "VSIM_72") (pintype "bidirectional"))
    )
    (net (code "90") (name "WAKEUP_3V3") (class "Default")
      (node (ref "D6") (pin "1") (pinfunction "C_1") (pintype "passive"))
      (node (ref "IC9") (pin "13") (pinfunction "B7_13") (pintype "bidirectional"))
      (node (ref "R43") (pin "1") (pinfunction "1_1") (pintype "passive"))
      (node (ref "S2") (pin "3") (pinfunction "3_3") (pintype "passive"))
      (node (ref "S2") (pin "4") (pinfunction "4_4") (pintype "passive"))
      (node (ref "S2") (pin "5") (pinfunction "3_5") (pintype "passive"))
      (node (ref "S2") (pin "6") (pinfunction "4_6") (pintype "passive"))
    )
    (net (code "91") (name "unconnected-(CON1-ID-Pad4)") (class "Default")
      (node (ref "CON1") (pin "4") (pinfunction "ID_4") (pintype "passive"))
    )
    (net (code "92") (name "unconnected-(CON3-VPP-PadC6)") (class "Default")
      (node (ref "CON3") (pin "C6") (pinfunction "VPP_C6") (pintype "bidirectional"))
    )
    (net (code "93") (name "unconnected-(IC1-AT_IN-Pad6)") (class "Default")
      (node (ref "IC1") (pin "6") (pinfunction "AT_IN_6") (pintype "bidirectional"))
    )
    (net (code "94") (name "unconnected-(IC1-DEBUG_SEL-Pad84)") (class "Default")
      (node (ref "IC1") (pin "84") (pinfunction "DEBUG_SEL_84") (pintype "bidirectional"))
    )
    (net (code "95") (name "unconnected-(IC1-DEBUG_{slash}RST-Pad82)") (class "Default")
      (node (ref "IC1") (pin "82") (pinfunction "DEBUG_/RST_82") (pintype "bidirectional"))
    )
    (net (code "96") (name "unconnected-(IC1-EJ_TCK-Pad10)") (class "Default")
      (node (ref "IC1") (pin "10") (pinfunction "EJ_TCK_10") (pintype "bidirectional"))
    )
    (net (code "97") (name "unconnected-(IC1-EJ_TDI-Pad14)") (class "Default")
      (node (ref "IC1") (pin "14") (pinfunction "EJ_TDI_14") (pintype "bidirectional"))
    )
    (net (code "98") (name "unconnected-(IC1-EJ_TDO-Pad12)") (class "Default")
      (node (ref "IC1") (pin "12") (pinfunction "EJ_TDO_12") (pintype "bidirectional"))
    )
    (net (code "99") (name "unconnected-(IC1-EJ_TMS-Pad16)") (class "Default")
      (node (ref "IC1") (pin "16") (pinfunction "EJ_TMS_16") (pintype "bidirectional"))
    )
    (net (code "100") (name "unconnected-(IC1-EJ_TRST-Pad18)") (class "Default")
      (node (ref "IC1") (pin "18") (pinfunction "EJ_TRST_18") (pintype "bidirectional"))
    )
    (net (code "101") (name "unconnected-(IC1-EXT_ALARM-Pad13)") (class "Default")
      (node (ref "IC1") (pin "13") (pinfunction "EXT_ALARM_13") (pintype "bidirectional"))
    )
    (net (code "102") (name "unconnected-(IC1-PMU_AT_OUT-Pad8)") (class "Default")
      (node (ref "IC1") (pin "8") (pinfunction "PMU_AT_OUT_8") (pintype "bidirectional"))
    )
    (net (code "103") (name "unconnected-(IC1-RESERVED1-Pad62)") (class "Default")
      (node (ref "IC1") (pin "62") (pinfunction "RESERVED1_62") (pintype "bidirectional"))
    )
    (net (code "104") (name "unconnected-(IC1-RESERVED2-Pad64)") (class "Default")
      (node (ref "IC1") (pin "64") (pinfunction "RESERVED2_64") (pintype "bidirectional"))
    )
    (net (code "105") (name "unconnected-(IC1-RESERVED3-Pad67)") (class "Default")
      (node (ref "IC1") (pin "67") (pinfunction "RESERVED3_67") (pintype "bidirectional"))
    )
    (net (code "106") (name "unconnected-(IC1-RESERVED4-Pad69)") (class "Default")
      (node (ref "IC1") (pin "69") (pinfunction "RESERVED4_69") (pintype "bidirectional"))
    )
    (net (code "107") (name "unconnected-(IC1-RESERVED5-Pad44)") (class "Default")
      (node (ref "IC1") (pin "44") (pinfunction "RESERVED5_44") (pintype "bidirectional"))
    )
    (net (code "108") (name "unconnected-(IC1-RESERVED6-Pad47)") (class "Default")
      (node (ref "IC1") (pin "47") (pinfunction "RESERVED6_47") (pintype "bidirectional"))
    )
    (net (code "109") (name "unconnected-(IC1-RESERVED7-Pad49)") (class "Default")
      (node (ref "IC1") (pin "49") (pinfunction "RESERVED7_49") (pintype "bidirectional"))
    )
    (net (code "110") (name "unconnected-(IC1-RESERVED8-Pad66)") (class "Default")
      (node (ref "IC1") (pin "66") (pinfunction "RESERVED8_66") (pintype "bidirectional"))
    )
    (net (code "111") (name "unconnected-(IC1-RESERVED9-Pad68)") (class "Default")
      (node (ref "IC1") (pin "68") (pinfunction "RESERVED9_68") (pintype "bidirectional"))
    )
    (net (code "112") (name "unconnected-(IC1-RESERVED10-Pad71)") (class "Default")
      (node (ref "IC1") (pin "71") (pinfunction "RESERVED10_71") (pintype "bidirectional"))
    )
    (net (code "113") (name "unconnected-(IC1-RESERVED11-Pad73)") (class "Default")
      (node (ref "IC1") (pin "73") (pinfunction "RESERVED11_73") (pintype "bidirectional"))
    )
    (net (code "114") (name "unconnected-(IC1-RESERVED12-Pad89)") (class "Default")
      (node (ref "IC1") (pin "89") (pinfunction "RESERVED12_89") (pintype "bidirectional"))
    )
    (net (code "115") (name "unconnected-(IC1-RESERVED13-Pad78)") (class "Default")
      (node (ref "IC1") (pin "78") (pinfunction "RESERVED13_78") (pintype "bidirectional"))
    )
    (net (code "116") (name "unconnected-(IC1-RESERVED14-Pad11)") (class "Default")
      (node (ref "IC1") (pin "11") (pinfunction "RESERVED14_11") (pintype "bidirectional"))
    )
    (net (code "117") (name "unconnected-(IC1-RESERVED15-Pad54)") (class "Default")
      (node (ref "IC1") (pin "54") (pinfunction "RESERVED15_54") (pintype "bidirectional"))
    )
    (net (code "118") (name "unconnected-(IC1-RESERVED16-Pad70)") (class "Default")
      (node (ref "IC1") (pin "70") (pinfunction "RESERVED16_70") (pintype "bidirectional"))
    )
    (net (code "119") (name "unconnected-(IC1-RFFE_SCLK-Pad23)") (class "Default")
      (node (ref "IC1") (pin "23") (pinfunction "RFFE_SCLK_23") (pintype "bidirectional"))
    )
    (net (code "120") (name "unconnected-(IC1-RFFE_SDATA-Pad24)") (class "Default")
      (node (ref "IC1") (pin "24") (pinfunction "RFFE_SDATA_24") (pintype "bidirectional"))
    )
    (net (code "121") (name "unconnected-(IC1-UART0_CTS{slash}GPIO25-Pad20)") (class "Default")
      (node (ref "IC1") (pin "20") (pinfunction "UART0_CTS/GPIO25_20") (pintype "bidirectional"))
    )
    (net (code "122") (name "unconnected-(IC1-UART0_RTS{slash}GPIO26-Pad19)") (class "Default")
      (node (ref "IC1") (pin "19") (pinfunction "UART0_RTS/GPIO26_19") (pintype "bidirectional"))
    )
    (net (code "123") (name "unconnected-(IC1-VBACKUP-Pad85)") (class "Default")
      (node (ref "IC1") (pin "85") (pinfunction "VBACKUP_85") (pintype "bidirectional"))
    )
    (net (code "124") (name "unconnected-(IC1-VCAP-Pad80)") (class "Default")
      (node (ref "IC1") (pin "80") (pinfunction "VCAP_80") (pintype "bidirectional"))
    )
    (net (code "125") (name "unconnected-(IC1-VDDIO-Pad87)") (class "Default")
      (node (ref "IC1") (pin "87") (pinfunction "VDDIO_87") (pintype "bidirectional"))
    )
    (net (code "126") (name "unconnected-(IC1-VDD_AUX-Pad91)") (class "Default")
      (node (ref "IC1") (pin "91") (pinfunction "VDD_AUX_91") (pintype "bidirectional"))
    )
    (net (code "127") (name "unconnected-(IC3-ADBUS2-Pad14)") (class "Default")
      (node (ref "IC3") (pin "14") (pinfunction "ADBUS2_14") (pintype "bidirectional"))
    )
    (net (code "128") (name "unconnected-(IC3-ADBUS3-Pad15)") (class "Default")
      (node (ref "IC3") (pin "15") (pinfunction "ADBUS3_15") (pintype "bidirectional"))
    )
    (net (code "129") (name "unconnected-(IC3-ADBUS4-Pad17)") (class "Default")
      (node (ref "IC3") (pin "17") (pinfunction "ADBUS4_17") (pintype "bidirectional"))
    )
    (net (code "130") (name "unconnected-(IC3-ADBUS5-Pad18)") (class "Default")
      (node (ref "IC3") (pin "18") (pinfunction "ADBUS5_18") (pintype "bidirectional"))
    )
    (net (code "131") (name "unconnected-(IC3-ADBUS6-Pad19)") (class "Default")
      (node (ref "IC3") (pin "19") (pinfunction "ADBUS6_19") (pintype "bidirectional"))
    )
    (net (code "132") (name "unconnected-(IC3-ADBUS7-Pad20)") (class "Default")
      (node (ref "IC3") (pin "20") (pinfunction "ADBUS7_20") (pintype "bidirectional"))
    )
    (net (code "133") (name "unconnected-(IC3-BDBUS2-Pad24)") (class "Default")
      (node (ref "IC3") (pin "24") (pinfunction "BDBUS2_24") (pintype "bidirectional"))
    )
    (net (code "134") (name "unconnected-(IC3-BDBUS3-Pad25)") (class "Default")
      (node (ref "IC3") (pin "25") (pinfunction "BDBUS3_25") (pintype "bidirectional"))
    )
    (net (code "135") (name "unconnected-(IC3-BDBUS4-Pad26)") (class "Default")
      (node (ref "IC3") (pin "26") (pinfunction "BDBUS4_26") (pintype "bidirectional"))
    )
    (net (code "136") (name "unconnected-(IC3-BDBUS5-Pad27)") (class "Default")
      (node (ref "IC3") (pin "27") (pinfunction "BDBUS5_27") (pintype "bidirectional"))
    )
    (net (code "137") (name "unconnected-(IC3-BDBUS6-Pad28)") (class "Default")
      (node (ref "IC3") (pin "28") (pinfunction "BDBUS6_28") (pintype "bidirectional"))
    )
    (net (code "138") (name "unconnected-(IC3-BDBUS7-Pad29)") (class "Default")
      (node (ref "IC3") (pin "29") (pinfunction "BDBUS7_29") (pintype "bidirectional"))
    )
    (net (code "139") (name "unconnected-(IC3-CDBUS4-Pad37)") (class "Default")
      (node (ref "IC3") (pin "37") (pinfunction "CDBUS4_37") (pintype "bidirectional"))
    )
    (net (code "140") (name "unconnected-(IC3-CDBUS5-Pad38)") (class "Default")
      (node (ref "IC3") (pin "38") (pinfunction "CDBUS5_38") (pintype "bidirectional"))
    )
    (net (code "141") (name "unconnected-(IC3-CDBUS6-Pad39)") (class "Default")
      (node (ref "IC3") (pin "39") (pinfunction "CDBUS6_39") (pintype "bidirectional"))
    )
    (net (code "142") (name "unconnected-(IC3-CDBUS7-Pad40)") (class "Default")
      (node (ref "IC3") (pin "40") (pinfunction "CDBUS7_40") (pintype "bidirectional"))
    )
    (net (code "143") (name "unconnected-(IC3-DDBUS0-Pad42)") (class "Default")
      (node (ref "IC3") (pin "42") (pinfunction "DDBUS0_42") (pintype "bidirectional"))
    )
    (net (code "144") (name "unconnected-(IC3-DDBUS1-Pad46)") (class "Default")
      (node (ref "IC3") (pin "46") (pinfunction "DDBUS1_46") (pintype "bidirectional"))
    )
    (net (code "145") (name "unconnected-(IC3-DDBUS2-Pad47)") (class "Default")
      (node (ref "IC3") (pin "47") (pinfunction "DDBUS2_47") (pintype "bidirectional"))
    )
    (net (code "146") (name "unconnected-(IC3-DDBUS3-Pad48)") (class "Default")
      (node (ref "IC3") (pin "48") (pinfunction "DDBUS3_48") (pintype "bidirectional"))
    )
    (net (code "147") (name "unconnected-(IC3-DDBUS4-Pad49)") (class "Default")
      (node (ref "IC3") (pin "49") (pinfunction "DDBUS4_49") (pintype "bidirectional"))
    )
    (net (code "148") (name "unconnected-(IC3-DDBUS5-Pad51)") (class "Default")
      (node (ref "IC3") (pin "51") (pinfunction "DDBUS5_51") (pintype "bidirectional"))
    )
    (net (code "149") (name "unconnected-(IC3-DDBUS6-Pad52)") (class "Default")
      (node (ref "IC3") (pin "52") (pinfunction "DDBUS6_52") (pintype "bidirectional"))
    )
    (net (code "150") (name "unconnected-(IC3-DDBUS7-Pad53)") (class "Default")
      (node (ref "IC3") (pin "53") (pinfunction "DDBUS7_53") (pintype "bidirectional"))
    )
    (net (code "151") (name "unconnected-(IC3-EECLK-Pad56)") (class "Default")
      (node (ref "IC3") (pin "56") (pinfunction "EECLK_56") (pintype "bidirectional"))
    )
    (net (code "152") (name "unconnected-(IC3-EECS-Pad1)") (class "Default")
      (node (ref "IC3") (pin "1") (pinfunction "EECS_1") (pintype "bidirectional"))
    )
    (net (code "153") (name "unconnected-(IC3-EEDATA-Pad55)") (class "Default")
      (node (ref "IC3") (pin "55") (pinfunction "EEDATA_55") (pintype "output"))
    )
    (net (code "154") (name "unconnected-(IC3-PWREN#-Pad54)") (class "Default")
      (node (ref "IC3") (pin "54") (pinfunction "PWREN#_54") (pintype "output"))
    )
    (net (code "155") (name "unconnected-(IC3-SUSPEND#-Pad30)") (class "Default")
      (node (ref "IC3") (pin "30") (pinfunction "SUSPEND#_30") (pintype "output"))
    )
    (net (code "156") (name "unconnected-(MS1-AREF-Pad3)") (class "Default")
      (node (ref "MS1") (pin "3") (pinfunction "AREF_3") (pintype "passive"))
    )
    (net (code "157") (name "unconnected-(MS1-EN-Pad27)") (class "Default")
      (node (ref "MS1") (pin "27") (pinfunction "EN_27") (pintype "passive"))
    )
    (net (code "158") (name "unconnected-(MS1-GPIO5-Pad19)") (class "Default")
      (node (ref "MS1") (pin "19") (pinfunction "GPIO5_19") (pintype "bidirectional"))
    )
    (net (code "159") (name "unconnected-(MS1-GPIO9-Pad21)") (class "Default")
      (node (ref "MS1") (pin "21") (pinfunction "GPIO9_21") (pintype "bidirectional"))
    )
    (net (code "160") (name "unconnected-(MS1-GPIO10-Pad22)") (class "Default")
      (node (ref "MS1") (pin "22") (pinfunction "GPIO10_22") (pintype "bidirectional"))
    )
    (net (code "161") (name "unconnected-(MS1-GPIO11-Pad23)") (class "Default")
      (node (ref "MS1") (pin "23") (pinfunction "GPIO11_23") (pintype "bidirectional"))
    )
    (net (code "162") (name "unconnected-(MS1-GPIO12-Pad24)") (class "Default")
      (node (ref "MS1") (pin "24") (pinfunction "GPIO12_24") (pintype "bidirectional"))
    )
    (net (code "163") (name "unconnected-(MS1-GPIO13-Pad25)") (class "Default")
      (node (ref "MS1") (pin "25") (pinfunction "GPIO13_25") (pintype "bidirectional"))
    )
    (net (code "164") (name "unconnected-(MS1-GPIOA2-Pad7)") (class "Default")
      (node (ref "MS1") (pin "7") (pinfunction "GPIOA2_7") (pintype "bidirectional"))
    )
    (net (code "165") (name "unconnected-(MS1-GPIOA3-Pad8)") (class "Default")
      (node (ref "MS1") (pin "8") (pinfunction "GPIOA3_8") (pintype "bidirectional"))
    )
    (net (code "166") (name "unconnected-(MS1-GPIOA4-Pad9)") (class "Default")
      (node (ref "MS1") (pin "9") (pinfunction "GPIOA4_9") (pintype "bidirectional"))
    )
    (net (code "167") (name "unconnected-(MS1-NC-Pad16)") (class "Default")
      (node (ref "MS1") (pin "16") (pinfunction "NC_16") (pintype "passive"))
    )
    (net (code "168") (name "{slash}RESET_3V3") (class "Default")
      (node (ref "IC9") (pin "12") (pinfunction "B8_12") (pintype "bidirectional"))
      (node (ref "MS1") (pin "1") (pinfunction "~{RESET}_1") (pintype "input"))
    )
  )
)
